# Mem_Switch_V1_1.net
KiCad netlist of a schematic drawn in EAGLE
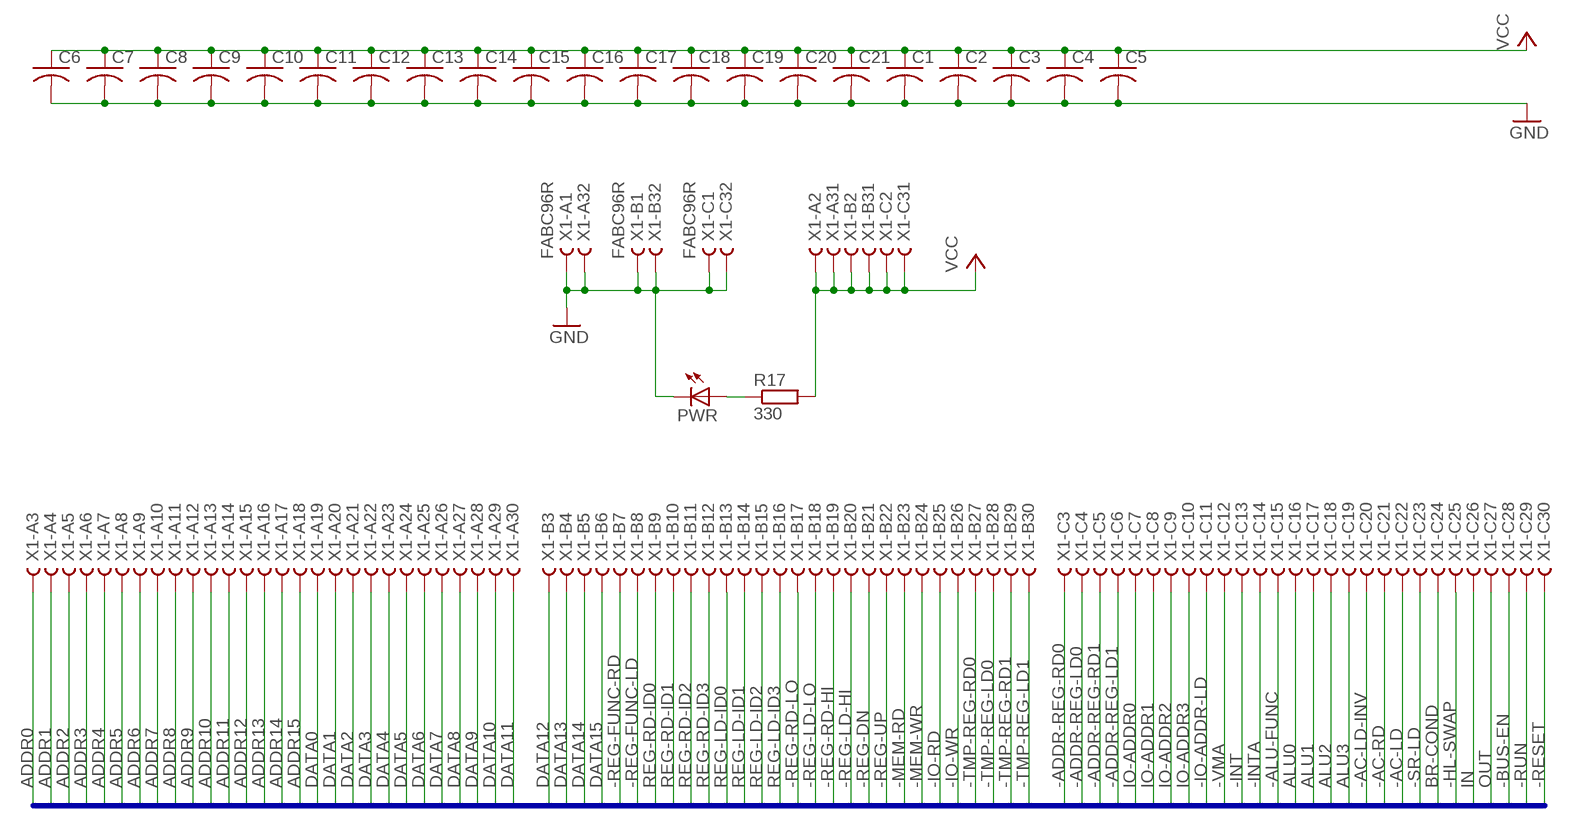
[diagram p0: schematic, sheet 1]
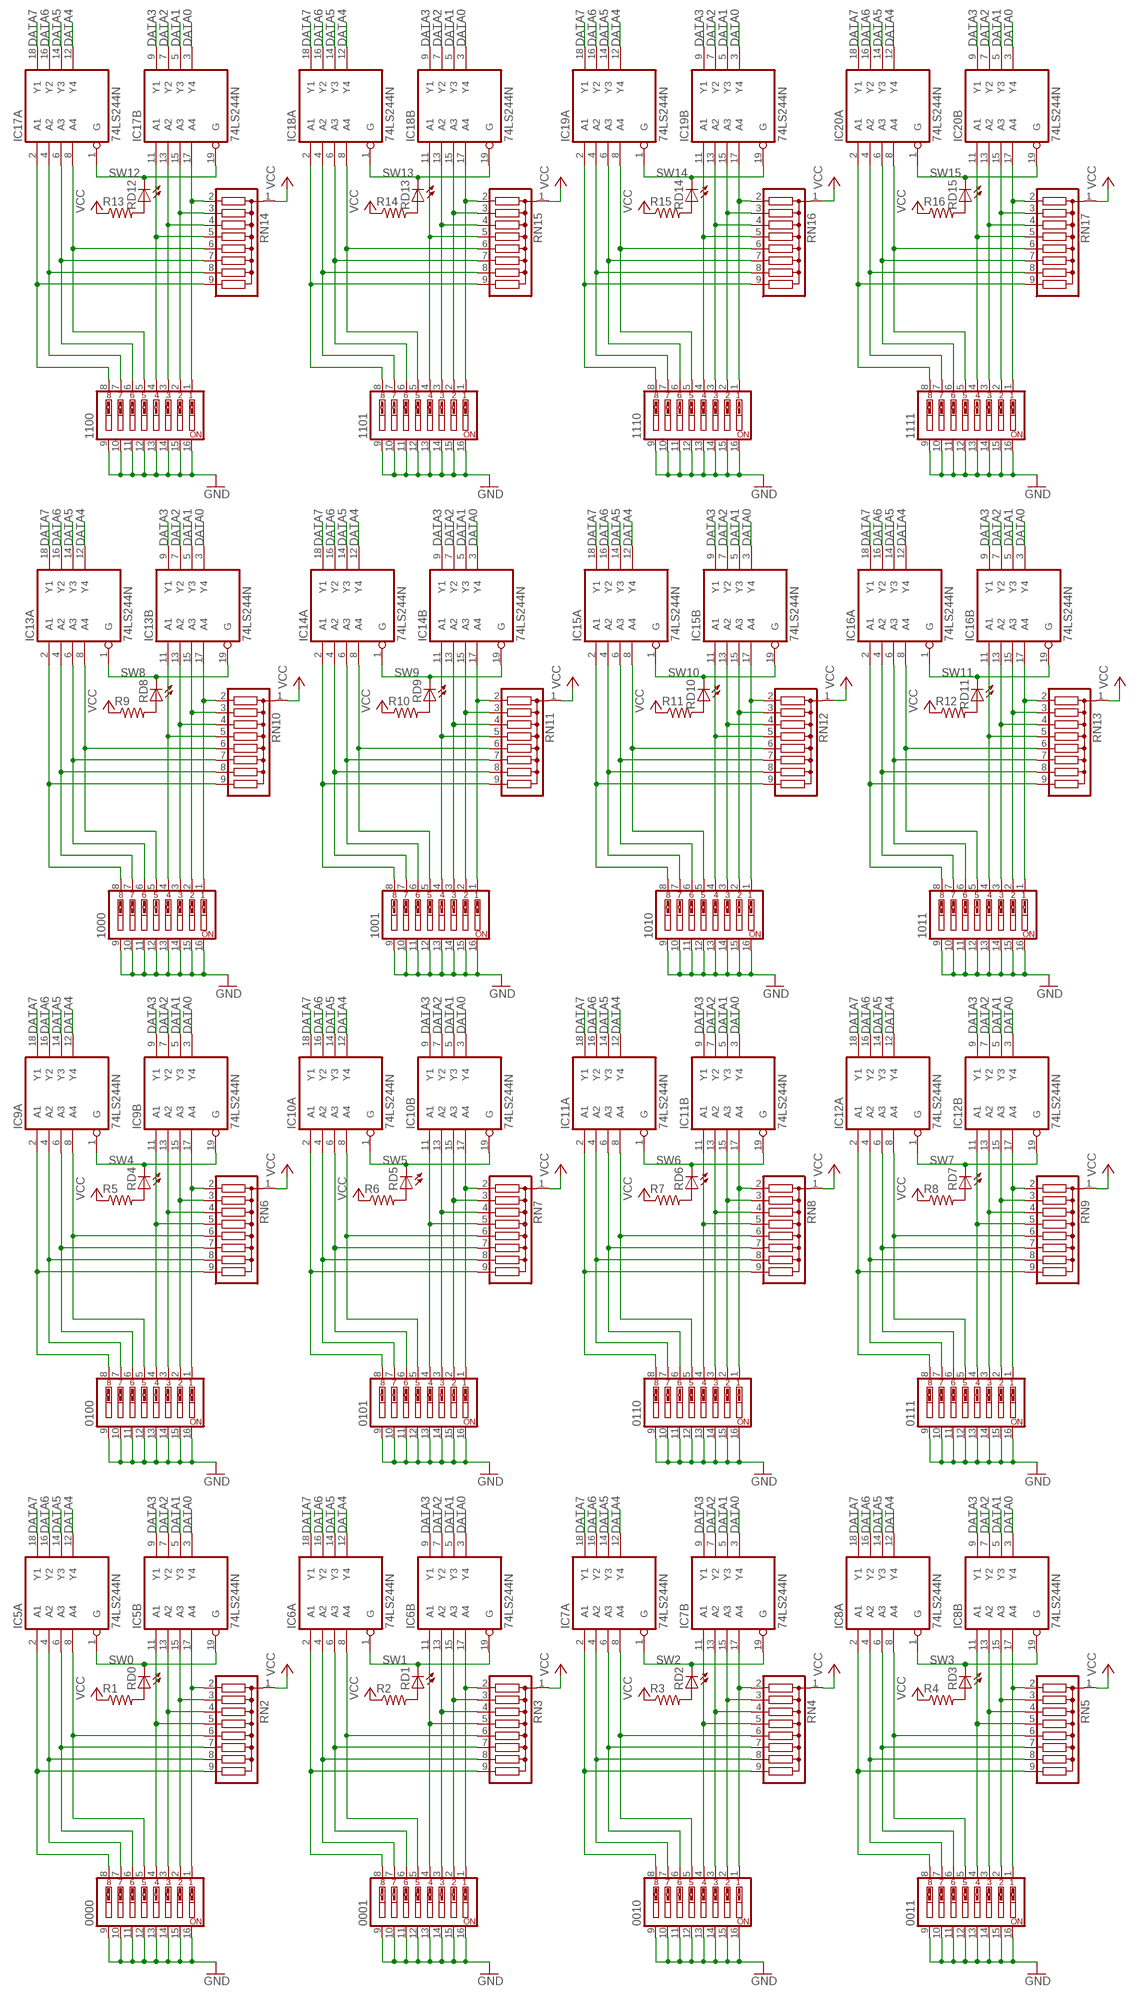
[diagram p1: schematic, sheet 2]
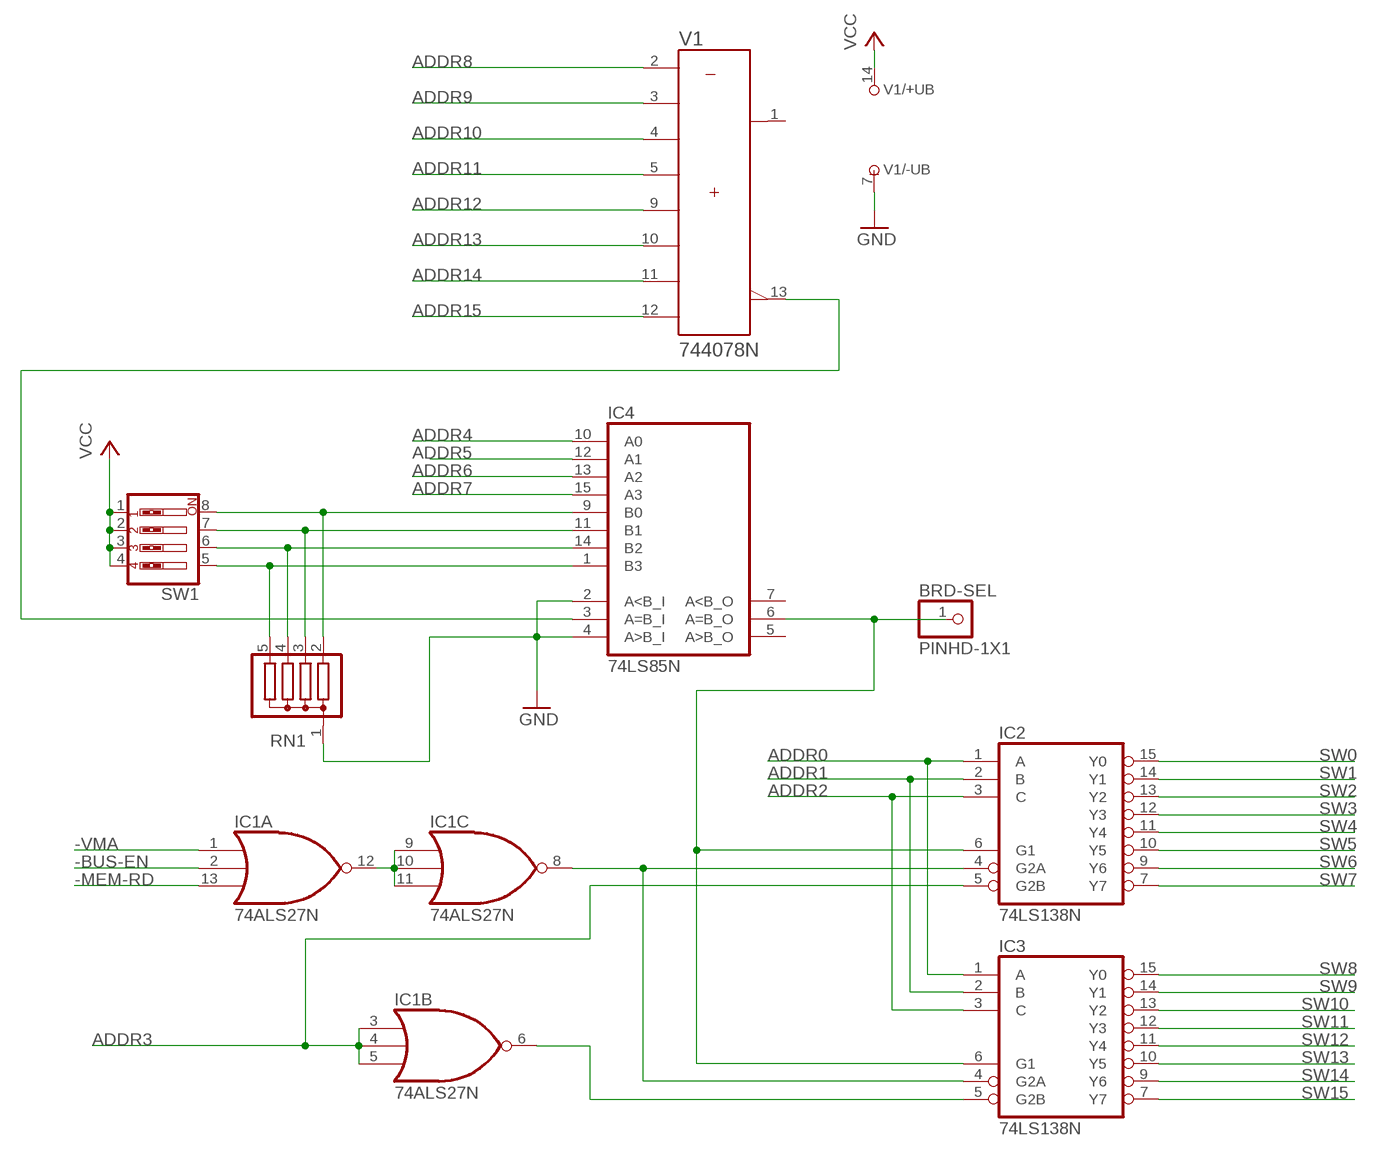
[diagram p2: schematic, sheet 3]

(export (version "E")
  (design (tool "Eeschema 10.0.6"))
  (components
    (comp (ref "0000")
      (value "SW_DIP-8")
      (footprint "eagle-import:EDG-08")
      (libsource (lib "eagle-import") (part "SW_DIP-8"))
    )
    (comp (ref "0001")
      (value "SW_DIP-8")
      (footprint "eagle-import:EDG-08")
      (libsource (lib "eagle-import") (part "SW_DIP-8"))
    )
    (comp (ref "0010")
      (value "SW_DIP-8")
      (footprint "eagle-import:EDG-08")
      (libsource (lib "eagle-import") (part "SW_DIP-8"))
    )
    (comp (ref "0011")
      (value "SW_DIP-8")
      (footprint "eagle-import:EDG-08")
      (libsource (lib "eagle-import") (part "SW_DIP-8"))
    )
    (comp (ref "0100")
      (value "SW_DIP-8")
      (footprint "eagle-import:EDG-08")
      (libsource (lib "eagle-import") (part "SW_DIP-8"))
    )
    (comp (ref "0101")
      (value "SW_DIP-8")
      (footprint "eagle-import:EDG-08")
      (libsource (lib "eagle-import") (part "SW_DIP-8"))
    )
    (comp (ref "0110")
      (value "SW_DIP-8")
      (footprint "eagle-import:EDG-08")
      (libsource (lib "eagle-import") (part "SW_DIP-8"))
    )
    (comp (ref "0111")
      (value "SW_DIP-8")
      (footprint "eagle-import:EDG-08")
      (libsource (lib "eagle-import") (part "SW_DIP-8"))
    )
    (comp (ref "1000")
      (value "SW_DIP-8")
      (footprint "eagle-import:EDG-08")
      (libsource (lib "eagle-import") (part "SW_DIP-8"))
    )
    (comp (ref "1001")
      (value "SW_DIP-8")
      (footprint "eagle-import:EDG-08")
      (libsource (lib "eagle-import") (part "SW_DIP-8"))
    )
    (comp (ref "1010")
      (value "SW_DIP-8")
      (footprint "eagle-import:EDG-08")
      (libsource (lib "eagle-import") (part "SW_DIP-8"))
    )
    (comp (ref "1011")
      (value "SW_DIP-8")
      (footprint "eagle-import:EDG-08")
      (libsource (lib "eagle-import") (part "SW_DIP-8"))
    )
    (comp (ref "1100")
      (value "SW_DIP-8")
      (footprint "eagle-import:EDG-08")
      (libsource (lib "eagle-import") (part "SW_DIP-8"))
    )
    (comp (ref "1101")
      (value "SW_DIP-8")
      (footprint "eagle-import:EDG-08")
      (libsource (lib "eagle-import") (part "SW_DIP-8"))
    )
    (comp (ref "1110")
      (value "SW_DIP-8")
      (footprint "eagle-import:EDG-08")
      (libsource (lib "eagle-import") (part "SW_DIP-8"))
    )
    (comp (ref "1111")
      (value "SW_DIP-8")
      (footprint "eagle-import:EDG-08")
      (libsource (lib "eagle-import") (part "SW_DIP-8"))
    )
    (comp (ref "IC5")
      (value "74LS244N")
      (footprint "eagle-import:DIL20")
      (libsource (lib "eagle-import") (part "74xx-us_88_74244NLS"))
    )
    (comp (ref "IC6")
      (value "74LS244N")
      (footprint "eagle-import:DIL20")
      (libsource (lib "eagle-import") (part "74xx-us_88_74244NLS"))
    )
    (comp (ref "IC7")
      (value "74LS244N")
      (footprint "eagle-import:DIL20")
      (libsource (lib "eagle-import") (part "74xx-us_88_74244NLS"))
    )
    (comp (ref "IC8")
      (value "74LS244N")
      (footprint "eagle-import:DIL20")
      (libsource (lib "eagle-import") (part "74xx-us_88_74244NLS"))
    )
    (comp (ref "IC9")
      (value "74LS244N")
      (footprint "eagle-import:DIL20")
      (libsource (lib "eagle-import") (part "74xx-us_88_74244NLS"))
    )
    (comp (ref "IC10")
      (value "74LS244N")
      (footprint "eagle-import:DIL20")
      (libsource (lib "eagle-import") (part "74xx-us_88_74244NLS"))
    )
    (comp (ref "IC11")
      (value "74LS244N")
      (footprint "eagle-import:DIL20")
      (libsource (lib "eagle-import") (part "74xx-us_88_74244NLS"))
    )
    (comp (ref "IC12")
      (value "74LS244N")
      (footprint "eagle-import:DIL20")
      (libsource (lib "eagle-import") (part "74xx-us_88_74244NLS"))
    )
    (comp (ref "IC13")
      (value "74LS244N")
      (footprint "eagle-import:DIL20")
      (libsource (lib "eagle-import") (part "74xx-us_88_74244NLS"))
    )
    (comp (ref "IC14")
      (value "74LS244N")
      (footprint "eagle-import:DIL20")
      (libsource (lib "eagle-import") (part "74xx-us_88_74244NLS"))
    )
    (comp (ref "IC15")
      (value "74LS244N")
      (footprint "eagle-import:DIL20")
      (libsource (lib "eagle-import") (part "74xx-us_88_74244NLS"))
    )
    (comp (ref "IC16")
      (value "74LS244N")
      (footprint "eagle-import:DIL20")
      (libsource (lib "eagle-import") (part "74xx-us_88_74244NLS"))
    )
    (comp (ref "IC17")
      (value "74LS244N")
      (footprint "eagle-import:DIL20")
      (libsource (lib "eagle-import") (part "74xx-us_88_74244NLS"))
    )
    (comp (ref "IC18")
      (value "74LS244N")
      (footprint "eagle-import:DIL20")
      (libsource (lib "eagle-import") (part "74xx-us_88_74244NLS"))
    )
    (comp (ref "IC19")
      (value "74LS244N")
      (footprint "eagle-import:DIL20")
      (libsource (lib "eagle-import") (part "74xx-us_88_74244NLS"))
    )
    (comp (ref "IC20")
      (value "74LS244N")
      (footprint "eagle-import:DIL20")
      (libsource (lib "eagle-import") (part "74xx-us_88_74244NLS"))
    )
    (comp (ref "R1")
      (value "R-US_0207/10")
      (footprint "eagle-import:0207_10")
      (libsource (lib "eagle-import") (part "R-US_0207/10"))
    )
    (comp (ref "R2")
      (value "R-US_0207/10")
      (footprint "eagle-import:0207_10")
      (libsource (lib "eagle-import") (part "R-US_0207/10"))
    )
    (comp (ref "R3")
      (value "R-US_0207/10")
      (footprint "eagle-import:0207_10")
      (libsource (lib "eagle-import") (part "R-US_0207/10"))
    )
    (comp (ref "R4")
      (value "R-US_0207/10")
      (footprint "eagle-import:0207_10")
      (libsource (lib "eagle-import") (part "R-US_0207/10"))
    )
    (comp (ref "R5")
      (value "R-US_0207/10")
      (footprint "eagle-import:0207_10")
      (libsource (lib "eagle-import") (part "R-US_0207/10"))
    )
    (comp (ref "R6")
      (value "R-US_0207/10")
      (footprint "eagle-import:0207_10")
      (libsource (lib "eagle-import") (part "R-US_0207/10"))
    )
    (comp (ref "R7")
      (value "R-US_0207/10")
      (footprint "eagle-import:0207_10")
      (libsource (lib "eagle-import") (part "R-US_0207/10"))
    )
    (comp (ref "R8")
      (value "R-US_0207/10")
      (footprint "eagle-import:0207_10")
      (libsource (lib "eagle-import") (part "R-US_0207/10"))
    )
    (comp (ref "R9")
      (value "R-US_0207/10")
      (footprint "eagle-import:0207_10")
      (libsource (lib "eagle-import") (part "R-US_0207/10"))
    )
    (comp (ref "R10")
      (value "R-US_0207/10")
      (footprint "eagle-import:0207_10")
      (libsource (lib "eagle-import") (part "R-US_0207/10"))
    )
    (comp (ref "R11")
      (value "R-US_0207/10")
      (footprint "eagle-import:0207_10")
      (libsource (lib "eagle-import") (part "R-US_0207/10"))
    )
    (comp (ref "R12")
      (value "R-US_0207/10")
      (footprint "eagle-import:0207_10")
      (libsource (lib "eagle-import") (part "R-US_0207/10"))
    )
    (comp (ref "R13")
      (value "R-US_0207/10")
      (footprint "eagle-import:0207_10")
      (libsource (lib "eagle-import") (part "R-US_0207/10"))
    )
    (comp (ref "R14")
      (value "R-US_0207/10")
      (footprint "eagle-import:0207_10")
      (libsource (lib "eagle-import") (part "R-US_0207/10"))
    )
    (comp (ref "R15")
      (value "R-US_0207/10")
      (footprint "eagle-import:0207_10")
      (libsource (lib "eagle-import") (part "R-US_0207/10"))
    )
    (comp (ref "R16")
      (value "R-US_0207/10")
      (footprint "eagle-import:0207_10")
      (libsource (lib "eagle-import") (part "R-US_0207/10"))
    )
    (comp (ref "RD0")
      (value "LED3MM")
      (footprint "eagle-import:LED3MM")
      (libsource (lib "eagle-import") (part "LED3MM"))
    )
    (comp (ref "RD1")
      (value "LED3MM")
      (footprint "eagle-import:LED3MM")
      (libsource (lib "eagle-import") (part "LED3MM"))
    )
    (comp (ref "RD2")
      (value "LED3MM")
      (footprint "eagle-import:LED3MM")
      (libsource (lib "eagle-import") (part "LED3MM"))
    )
    (comp (ref "RD3")
      (value "LED3MM")
      (footprint "eagle-import:LED3MM")
      (libsource (lib "eagle-import") (part "LED3MM"))
    )
    (comp (ref "RD4")
      (value "LED3MM")
      (footprint "eagle-import:LED3MM")
      (libsource (lib "eagle-import") (part "LED3MM"))
    )
    (comp (ref "RD5")
      (value "LED3MM")
      (footprint "eagle-import:LED3MM")
      (libsource (lib "eagle-import") (part "LED3MM"))
    )
    (comp (ref "RD6")
      (value "LED3MM")
      (footprint "eagle-import:LED3MM")
      (libsource (lib "eagle-import") (part "LED3MM"))
    )
    (comp (ref "RD7")
      (value "LED3MM")
      (footprint "eagle-import:LED3MM")
      (libsource (lib "eagle-import") (part "LED3MM"))
    )
    (comp (ref "RD8")
      (value "LED3MM")
      (footprint "eagle-import:LED3MM")
      (libsource (lib "eagle-import") (part "LED3MM"))
    )
    (comp (ref "RD9")
      (value "LED3MM")
      (footprint "eagle-import:LED3MM")
      (libsource (lib "eagle-import") (part "LED3MM"))
    )
    (comp (ref "RD10")
      (value "LED3MM")
      (footprint "eagle-import:LED3MM")
      (libsource (lib "eagle-import") (part "LED3MM"))
    )
    (comp (ref "RD11")
      (value "LED3MM")
      (footprint "eagle-import:LED3MM")
      (libsource (lib "eagle-import") (part "LED3MM"))
    )
    (comp (ref "RD12")
      (value "LED3MM")
      (footprint "eagle-import:LED3MM")
      (libsource (lib "eagle-import") (part "LED3MM"))
    )
    (comp (ref "RD13")
      (value "LED3MM")
      (footprint "eagle-import:LED3MM")
      (libsource (lib "eagle-import") (part "LED3MM"))
    )
    (comp (ref "RD14")
      (value "LED3MM")
      (footprint "eagle-import:LED3MM")
      (libsource (lib "eagle-import") (part "LED3MM"))
    )
    (comp (ref "RD15")
      (value "LED3MM")
      (footprint "eagle-import:LED3MM")
      (libsource (lib "eagle-import") (part "LED3MM"))
    )
    (comp (ref "RN2")
      (value "G08R")
      (footprint "eagle-import:SIL9")
      (libsource (lib "eagle-import") (part "G08R"))
    )
    (comp (ref "RN3")
      (value "G08R")
      (footprint "eagle-import:SIL9")
      (libsource (lib "eagle-import") (part "G08R"))
    )
    (comp (ref "RN4")
      (value "G08R")
      (footprint "eagle-import:SIL9")
      (libsource (lib "eagle-import") (part "G08R"))
    )
    (comp (ref "RN5")
      (value "G08R")
      (footprint "eagle-import:SIL9")
      (libsource (lib "eagle-import") (part "G08R"))
    )
    (comp (ref "RN6")
      (value "G08R")
      (footprint "eagle-import:SIL9")
      (libsource (lib "eagle-import") (part "G08R"))
    )
    (comp (ref "RN7")
      (value "G08R")
      (footprint "eagle-import:SIL9")
      (libsource (lib "eagle-import") (part "G08R"))
    )
    (comp (ref "RN8")
      (value "G08R")
      (footprint "eagle-import:SIL9")
      (libsource (lib "eagle-import") (part "G08R"))
    )
    (comp (ref "RN9")
      (value "G08R")
      (footprint "eagle-import:SIL9")
      (libsource (lib "eagle-import") (part "G08R"))
    )
    (comp (ref "RN10")
      (value "G08R")
      (footprint "eagle-import:SIL9")
      (libsource (lib "eagle-import") (part "G08R"))
    )
    (comp (ref "RN11")
      (value "G08R")
      (footprint "eagle-import:SIL9")
      (libsource (lib "eagle-import") (part "G08R"))
    )
    (comp (ref "RN12")
      (value "G08R")
      (footprint "eagle-import:SIL9")
      (libsource (lib "eagle-import") (part "G08R"))
    )
    (comp (ref "RN13")
      (value "G08R")
      (footprint "eagle-import:SIL9")
      (libsource (lib "eagle-import") (part "G08R"))
    )
    (comp (ref "RN14")
      (value "G08R")
      (footprint "eagle-import:SIL9")
      (libsource (lib "eagle-import") (part "G08R"))
    )
    (comp (ref "RN15")
      (value "G08R")
      (footprint "eagle-import:SIL9")
      (libsource (lib "eagle-import") (part "G08R"))
    )
    (comp (ref "RN16")
      (value "G08R")
      (footprint "eagle-import:SIL9")
      (libsource (lib "eagle-import") (part "G08R"))
    )
    (comp (ref "RN17")
      (value "G08R")
      (footprint "eagle-import:SIL9")
      (libsource (lib "eagle-import") (part "G08R"))
    )
    (comp (ref "C1")
      (value "C-US025-025X050")
      (footprint "eagle-import:C025-025X050")
      (libsource (lib "eagle-import") (part "C-US025-025X050"))
    )
    (comp (ref "C2")
      (value "C-US025-025X050")
      (footprint "eagle-import:C025-025X050")
      (libsource (lib "eagle-import") (part "C-US025-025X050"))
    )
    (comp (ref "C3")
      (value "C-US025-025X050")
      (footprint "eagle-import:C025-025X050")
      (libsource (lib "eagle-import") (part "C-US025-025X050"))
    )
    (comp (ref "C4")
      (value "C-US025-025X050")
      (footprint "eagle-import:C025-025X050")
      (libsource (lib "eagle-import") (part "C-US025-025X050"))
    )
    (comp (ref "C5")
      (value "C-US025-025X050")
      (footprint "eagle-import:C025-025X050")
      (libsource (lib "eagle-import") (part "C-US025-025X050"))
    )
    (comp (ref "C6")
      (value "C-US025-025X050")
      (footprint "eagle-import:C025-025X050")
      (libsource (lib "eagle-import") (part "C-US025-025X050"))
    )
    (comp (ref "C7")
      (value "C-US025-025X050")
      (footprint "eagle-import:C025-025X050")
      (libsource (lib "eagle-import") (part "C-US025-025X050"))
    )
    (comp (ref "C8")
      (value "C-US025-025X050")
      (footprint "eagle-import:C025-025X050")
      (libsource (lib "eagle-import") (part "C-US025-025X050"))
    )
    (comp (ref "C9")
      (value "C-US025-025X050")
      (footprint "eagle-import:C025-025X050")
      (libsource (lib "eagle-import") (part "C-US025-025X050"))
    )
    (comp (ref "C10")
      (value "C-US025-025X050")
      (footprint "eagle-import:C025-025X050")
      (libsource (lib "eagle-import") (part "C-US025-025X050"))
    )
    (comp (ref "C11")
      (value "C-US025-025X050")
      (footprint "eagle-import:C025-025X050")
      (libsource (lib "eagle-import") (part "C-US025-025X050"))
    )
    (comp (ref "C12")
      (value "C-US025-025X050")
      (footprint "eagle-import:C025-025X050")
      (libsource (lib "eagle-import") (part "C-US025-025X050"))
    )
    (comp (ref "C13")
      (value "C-US025-025X050")
      (footprint "eagle-import:C025-025X050")
      (libsource (lib "eagle-import") (part "C-US025-025X050"))
    )
    (comp (ref "C14")
      (value "C-US025-025X050")
      (footprint "eagle-import:C025-025X050")
      (libsource (lib "eagle-import") (part "C-US025-025X050"))
    )
    (comp (ref "C15")
      (value "C-US025-025X050")
      (footprint "eagle-import:C025-025X050")
      (libsource (lib "eagle-import") (part "C-US025-025X050"))
    )
    (comp (ref "C16")
      (value "C-US025-025X050")
      (footprint "eagle-import:C025-025X050")
      (libsource (lib "eagle-import") (part "C-US025-025X050"))
    )
    (comp (ref "C17")
      (value "C-US025-025X050")
      (footprint "eagle-import:C025-025X050")
      (libsource (lib "eagle-import") (part "C-US025-025X050"))
    )
    (comp (ref "C18")
      (value "C-US025-025X050")
      (footprint "eagle-import:C025-025X050")
      (libsource (lib "eagle-import") (part "C-US025-025X050"))
    )
    (comp (ref "C19")
      (value "C-US025-025X050")
      (footprint "eagle-import:C025-025X050")
      (libsource (lib "eagle-import") (part "C-US025-025X050"))
    )
    (comp (ref "C20")
      (value "C-US025-025X050")
      (footprint "eagle-import:C025-025X050")
      (libsource (lib "eagle-import") (part "C-US025-025X050"))
    )
    (comp (ref "C21")
      (value "C-US025-025X050")
      (footprint "eagle-import:C025-025X050")
      (libsource (lib "eagle-import") (part "C-US025-025X050"))
    )
    (comp (ref "PWR")
      (value "LED5MM")
      (footprint "eagle-import:LED5MM")
      (libsource (lib "eagle-import") (part "led_LED5MM"))
    )
    (comp (ref "R17")
      (value "330")
      (footprint "eagle-import:0207_10")
      (libsource (lib "eagle-import") (part "R0207/10"))
    )
    (comp (ref "X1")
      (value "FABC96R")
      (footprint "eagle-import:FABC96R")
      (libsource (lib "eagle-import") (part "FABC96R"))
    )
    (comp (ref "BRD-SEL")
      (value "PINHD-1X1")
      (footprint "eagle-import:1X01")
      (libsource (lib "eagle-import") (part "PINHD-1X1"))
    )
    (comp (ref "IC1")
      (value "74ALS27N")
      (footprint "eagle-import:DIL14")
      (libsource (lib "eagle-import") (part "7427NALS"))
    )
    (comp (ref "IC2")
      (value "74LS138N")
      (footprint "eagle-import:DIL16")
      (libsource (lib "eagle-import") (part "74138NLS"))
    )
    (comp (ref "IC3")
      (value "74LS138N")
      (footprint "eagle-import:DIL16")
      (libsource (lib "eagle-import") (part "74138NLS"))
    )
    (comp (ref "IC4")
      (value "74LS85N")
      (footprint "eagle-import:DIL16")
      (libsource (lib "eagle-import") (part "7485NLS"))
    )
    (comp (ref "RN1")
      (value "G04R")
      (footprint "eagle-import:SIL5")
      (libsource (lib "eagle-import") (part "G04R"))
    )
    (comp (ref "SW1")
      (value "SW_DIP-4")
      (footprint "eagle-import:EDG-04")
      (libsource (lib "eagle-import") (part "SW_DIP-4"))
    )
    (comp (ref "V1")
      (value "744078N")
      (footprint "eagle-import:DIL14")
      (libsource (lib "eagle-import") (part "744078N"))
    )
  )
  (nets
    (net (code "1") (name "-AC-LD") (class "Default")
      (node (ref "X1") (pin "C22") (pinfunction "B_C22") (pintype "passive"))
    )
    (net (code "2") (name "-AC-LD-INV") (class "Default")
      (node (ref "X1") (pin "C20") (pinfunction "B_C20") (pintype "passive"))
    )
    (net (code "3") (name "-AC-RD") (class "Default")
      (node (ref "X1") (pin "C21") (pinfunction "B_C21") (pintype "passive"))
    )
    (net (code "4") (name "-ADDR-REG-LD0") (class "Default")
      (node (ref "X1") (pin "C4") (pinfunction "B_C4") (pintype "passive"))
    )
    (net (code "5") (name "-ADDR-REG-LD1") (class "Default")
      (node (ref "X1") (pin "C6") (pinfunction "B_C6") (pintype "passive"))
    )
    (net (code "6") (name "-ADDR-REG-RD0") (class "Default")
      (node (ref "X1") (pin "C3") (pinfunction "B_C3") (pintype "passive"))
    )
    (net (code "7") (name "-ADDR-REG-RD1") (class "Default")
      (node (ref "X1") (pin "C5") (pinfunction "B_C5") (pintype "passive"))
    )
    (net (code "8") (name "-ALU-FUNC") (class "Default")
      (node (ref "X1") (pin "C15") (pinfunction "B_C15") (pintype "passive"))
    )
    (net (code "9") (name "-BUS-EN") (class "Default")
      (node (ref "IC1") (pin "2") (pinfunction "I1_2") (pintype "input"))
      (node (ref "X1") (pin "C28") (pinfunction "B_C28") (pintype "passive"))
    )
    (net (code "10") (name "-HL-SWAP") (class "Default")
      (node (ref "X1") (pin "C25") (pinfunction "B_C25") (pintype "passive"))
    )
    (net (code "11") (name "-INT") (class "Default")
      (node (ref "X1") (pin "C13") (pinfunction "B_C13") (pintype "passive"))
    )
    (net (code "12") (name "-INTA") (class "Default")
      (node (ref "X1") (pin "C14") (pinfunction "B_C14") (pintype "passive"))
    )
    (net (code "13") (name "-IO-ADDR-LD") (class "Default")
      (node (ref "X1") (pin "C11") (pinfunction "B_C11") (pintype "passive"))
    )
    (net (code "14") (name "-IO-RD") (class "Default")
      (node (ref "X1") (pin "B25") (pinfunction "B_B25") (pintype "passive"))
    )
    (net (code "15") (name "-IO-WR") (class "Default")
      (node (ref "X1") (pin "B26") (pinfunction "B_B26") (pintype "passive"))
    )
    (net (code "16") (name "-MEM-RD") (class "Default")
      (node (ref "IC1") (pin "13") (pinfunction "I2_13") (pintype "input"))
      (node (ref "X1") (pin "B23") (pinfunction "B_B23") (pintype "passive"))
    )
    (net (code "17") (name "-MEM-WR") (class "Default")
      (node (ref "X1") (pin "B24") (pinfunction "B_B24") (pintype "passive"))
    )
    (net (code "18") (name "-REG-DN") (class "Default")
      (node (ref "X1") (pin "B21") (pinfunction "B_B21") (pintype "passive"))
    )
    (net (code "19") (name "-REG-FUNC-LD") (class "Default")
      (node (ref "X1") (pin "B8") (pinfunction "B_B8") (pintype "passive"))
    )
    (net (code "20") (name "-REG-FUNC-RD") (class "Default")
      (node (ref "X1") (pin "B7") (pinfunction "B_B7") (pintype "passive"))
    )
    (net (code "21") (name "-REG-LD-HI") (class "Default")
      (node (ref "X1") (pin "B20") (pinfunction "B_B20") (pintype "passive"))
    )
    (net (code "22") (name "-REG-LD-LO") (class "Default")
      (node (ref "X1") (pin "B18") (pinfunction "B_B18") (pintype "passive"))
    )
    (net (code "23") (name "-REG-RD-HI") (class "Default")
      (node (ref "X1") (pin "B19") (pinfunction "B_B19") (pintype "passive"))
    )
    (net (code "24") (name "-REG-RD-LO") (class "Default")
      (node (ref "X1") (pin "B17") (pinfunction "B_B17") (pintype "passive"))
    )
    (net (code "25") (name "-REG-UP") (class "Default")
      (node (ref "X1") (pin "B22") (pinfunction "B_B22") (pintype "passive"))
    )
    (net (code "26") (name "-RESET") (class "Default")
      (node (ref "X1") (pin "C30") (pinfunction "B_C30") (pintype "passive"))
    )
    (net (code "27") (name "-RUN") (class "Default")
      (node (ref "X1") (pin "C29") (pinfunction "B_C29") (pintype "passive"))
    )
    (net (code "28") (name "-SR-LD") (class "Default")
      (node (ref "X1") (pin "C23") (pinfunction "B_C23") (pintype "passive"))
    )
    (net (code "29") (name "-TMP-REG-LD0") (class "Default")
      (node (ref "X1") (pin "B28") (pinfunction "B_B28") (pintype "passive"))
    )
    (net (code "30") (name "-TMP-REG-LD1") (class "Default")
      (node (ref "X1") (pin "B30") (pinfunction "B_B30") (pintype "passive"))
    )
    (net (code "31") (name "-TMP-REG-RD0") (class "Default")
      (node (ref "X1") (pin "B27") (pinfunction "B_B27") (pintype "passive"))
    )
    (net (code "32") (name "-TMP-REG-RD1") (class "Default")
      (node (ref "X1") (pin "B29") (pinfunction "B_B29") (pintype "passive"))
    )
    (net (code "33") (name "-VMA") (class "Default")
      (node (ref "IC1") (pin "1") (pinfunction "I0_1") (pintype "input"))
      (node (ref "X1") (pin "C12") (pinfunction "B_C12") (pintype "passive"))
    )
    (net (code "34") (name "ADDR0") (class "Default")
      (node (ref "IC2") (pin "1") (pinfunction "A_1") (pintype "input"))
      (node (ref "IC3") (pin "1") (pinfunction "A_1") (pintype "input"))
      (node (ref "X1") (pin "A3") (pinfunction "B_A3") (pintype "passive"))
    )
    (net (code "35") (name "ADDR1") (class "Default")
      (node (ref "IC2") (pin "2") (pinfunction "B_2") (pintype "input"))
      (node (ref "IC3") (pin "2") (pinfunction "B_2") (pintype "input"))
      (node (ref "X1") (pin "A4") (pinfunction "B_A4") (pintype "passive"))
    )
    (net (code "36") (name "ADDR2") (class "Default")
      (node (ref "IC2") (pin "3") (pinfunction "C_3") (pintype "input"))
      (node (ref "IC3") (pin "3") (pinfunction "C_3") (pintype "input"))
      (node (ref "X1") (pin "A5") (pinfunction "B_A5") (pintype "passive"))
    )
    (net (code "37") (name "ADDR3") (class "Default")
      (node (ref "IC1") (pin "3") (pinfunction "I0_3") (pintype "input"))
      (node (ref "IC1") (pin "4") (pinfunction "I1_4") (pintype "input"))
      (node (ref "IC1") (pin "5") (pinfunction "I2_5") (pintype "input"))
      (node (ref "IC2") (pin "5") (pinfunction "G2B_5") (pintype "input"))
      (node (ref "X1") (pin "A6") (pinfunction "B_A6") (pintype "passive"))
    )
    (net (code "38") (name "ADDR4") (class "Default")
      (node (ref "IC4") (pin "10") (pinfunction "A0_10") (pintype "input"))
      (node (ref "X1") (pin "A7") (pinfunction "B_A7") (pintype "passive"))
    )
    (net (code "39") (name "ADDR5") (class "Default")
      (node (ref "IC4") (pin "12") (pinfunction "A1_12") (pintype "input"))
      (node (ref "X1") (pin "A8") (pinfunction "B_A8") (pintype "passive"))
    )
    (net (code "40") (name "ADDR6") (class "Default")
      (node (ref "IC4") (pin "13") (pinfunction "A2_13") (pintype "input"))
      (node (ref "X1") (pin "A9") (pinfunction "B_A9") (pintype "passive"))
    )
    (net (code "41") (name "ADDR7") (class "Default")
      (node (ref "IC4") (pin "15") (pinfunction "A3_15") (pintype "input"))
      (node (ref "X1") (pin "A10") (pinfunction "B_A10") (pintype "passive"))
    )
    (net (code "42") (name "ADDR8") (class "Default")
      (node (ref "V1") (pin "2") (pinfunction "A_2") (pintype "input"))
      (node (ref "X1") (pin "A11") (pinfunction "B_A11") (pintype "passive"))
    )
    (net (code "43") (name "ADDR9") (class "Default")
      (node (ref "V1") (pin "3") (pinfunction "B_3") (pintype "input"))
      (node (ref "X1") (pin "A12") (pinfunction "B_A12") (pintype "passive"))
    )
    (net (code "44") (name "ADDR10") (class "Default")
      (node (ref "V1") (pin "4") (pinfunction "C_4") (pintype "input"))
      (node (ref "X1") (pin "A13") (pinfunction "B_A13") (pintype "passive"))
    )
    (net (code "45") (name "ADDR11") (class "Default")
      (node (ref "V1") (pin "5") (pinfunction "D_5") (pintype "input"))
      (node (ref "X1") (pin "A14") (pinfunction "B_A14") (pintype "passive"))
    )
    (net (code "46") (name "ADDR12") (class "Default")
      (node (ref "V1") (pin "9") (pinfunction "E_9") (pintype "input"))
      (node (ref "X1") (pin "A15") (pinfunction "B_A15") (pintype "passive"))
    )
    (net (code "47") (name "ADDR13") (class "Default")
      (node (ref "V1") (pin "10") (pinfunction "F_10") (pintype "input"))
      (node (ref "X1") (pin "A16") (pinfunction "B_A16") (pintype "passive"))
    )
    (net (code "48") (name "ADDR14") (class "Default")
      (node (ref "V1") (pin "11") (pinfunction "G_11") (pintype "input"))
      (node (ref "X1") (pin "A17") (pinfunction "B_A17") (pintype "passive"))
    )
    (net (code "49") (name "ADDR15") (class "Default")
      (node (ref "V1") (pin "12") (pinfunction "H_12") (pintype "input"))
      (node (ref "X1") (pin "A18") (pinfunction "B_A18") (pintype "passive"))
    )
    (net (code "50") (name "ALU0") (class "Default")
      (node (ref "X1") (pin "C16") (pinfunction "B_C16") (pintype "passive"))
    )
    (net (code "51") (name "ALU1") (class "Default")
      (node (ref "X1") (pin "C17") (pinfunction "B_C17") (pintype "passive"))
    )
    (net (code "52") (name "ALU2") (class "Default")
      (node (ref "X1") (pin "C18") (pinfunction "B_C18") (pintype "passive"))
    )
    (net (code "53") (name "ALU3") (class "Default")
      (node (ref "X1") (pin "C19") (pinfunction "B_C19") (pintype "passive"))
    )
    (net (code "54") (name "BR-COND") (class "Default")
      (node (ref "X1") (pin "C24") (pinfunction "B_C24") (pintype "passive"))
    )
    (net (code "55") (name "DATA0") (class "Default")
      (node (ref "IC10") (pin "3") (pinfunction "Y4_3") (pintype "tri_state"))
      (node (ref "IC11") (pin "3") (pinfunction "Y4_3") (pintype "tri_state"))
      (node (ref "IC12") (pin "3") (pinfunction "Y4_3") (pintype "tri_state"))
      (node (ref "IC13") (pin "3") (pinfunction "Y4_3") (pintype "tri_state"))
      (node (ref "IC14") (pin "3") (pinfunction "Y4_3") (pintype "tri_state"))
      (node (ref "IC15") (pin "3") (pinfunction "Y4_3") (pintype "tri_state"))
      (node (ref "IC16") (pin "3") (pinfunction "Y4_3") (pintype "tri_state"))
      (node (ref "IC17") (pin "3") (pinfunction "Y4_3") (pintype "tri_state"))
      (node (ref "IC18") (pin "3") (pinfunction "Y4_3") (pintype "tri_state"))
      (node (ref "IC19") (pin "3") (pinfunction "Y4_3") (pintype "tri_state"))
      (node (ref "IC20") (pin "3") (pinfunction "Y4_3") (pintype "tri_state"))
      (node (ref "IC5") (pin "3") (pinfunction "Y4_3") (pintype "tri_state"))
      (node (ref "IC6") (pin "3") (pinfunction "Y4_3") (pintype "tri_state"))
      (node (ref "IC7") (pin "3") (pinfunction "Y4_3") (pintype "tri_state"))
      (node (ref "IC8") (pin "3") (pinfunction "Y4_3") (pintype "tri_state"))
      (node (ref "IC9") (pin "3") (pinfunction "Y4_3") (pintype "tri_state"))
      (node (ref "X1") (pin "A19") (pinfunction "B_A19") (pintype "passive"))
    )
    (net (code "56") (name "DATA1") (class "Default")
      (node (ref "IC10") (pin "5") (pinfunction "Y3_5") (pintype "tri_state"))
      (node (ref "IC11") (pin "5") (pinfunction "Y3_5") (pintype "tri_state"))
      (node (ref "IC12") (pin "5") (pinfunction "Y3_5") (pintype "tri_state"))
      (node (ref "IC13") (pin "5") (pinfunction "Y3_5") (pintype "tri_state"))
      (node (ref "IC14") (pin "5") (pinfunction "Y3_5") (pintype "tri_state"))
      (node (ref "IC15") (pin "5") (pinfunction "Y3_5") (pintype "tri_state"))
      (node (ref "IC16") (pin "5") (pinfunction "Y3_5") (pintype "tri_state"))
      (node (ref "IC17") (pin "5") (pinfunction "Y3_5") (pintype "tri_state"))
      (node (ref "IC18") (pin "5") (pinfunction "Y3_5") (pintype "tri_state"))
      (node (ref "IC19") (pin "5") (pinfunction "Y3_5") (pintype "tri_state"))
      (node (ref "IC20") (pin "5") (pinfunction "Y3_5") (pintype "tri_state"))
      (node (ref "IC5") (pin "5") (pinfunction "Y3_5") (pintype "tri_state"))
      (node (ref "IC6") (pin "5") (pinfunction "Y3_5") (pintype "tri_state"))
      (node (ref "IC7") (pin "5") (pinfunction "Y3_5") (pintype "tri_state"))
      (node (ref "IC8") (pin "5") (pinfunction "Y3_5") (pintype "tri_state"))
      (node (ref "IC9") (pin "5") (pinfunction "Y3_5") (pintype "tri_state"))
      (node (ref "X1") (pin "A20") (pinfunction "B_A20") (pintype "passive"))
    )
    (net (code "57") (name "DATA2") (class "Default")
      (node (ref "IC10") (pin "7") (pinfunction "Y2_7") (pintype "tri_state"))
      (node (ref "IC11") (pin "7") (pinfunction "Y2_7") (pintype "tri_state"))
      (node (ref "IC12") (pin "7") (pinfunction "Y2_7") (pintype "tri_state"))
      (node (ref "IC13") (pin "7") (pinfunction "Y2_7") (pintype "tri_state"))
      (node (ref "IC14") (pin "7") (pinfunction "Y2_7") (pintype "tri_state"))
      (node (ref "IC15") (pin "7") (pinfunction "Y2_7") (pintype "tri_state"))
      (node (ref "IC16") (pin "7") (pinfunction "Y2_7") (pintype "tri_state"))
      (node (ref "IC17") (pin "7") (pinfunction "Y2_7") (pintype "tri_state"))
      (node (ref "IC18") (pin "7") (pinfunction "Y2_7") (pintype "tri_state"))
      (node (ref "IC19") (pin "7") (pinfunction "Y2_7") (pintype "tri_state"))
      (node (ref "IC20") (pin "7") (pinfunction "Y2_7") (pintype "tri_state"))
      (node (ref "IC5") (pin "7") (pinfunction "Y2_7") (pintype "tri_state"))
      (node (ref "IC6") (pin "7") (pinfunction "Y2_7") (pintype "tri_state"))
      (node (ref "IC7") (pin "7") (pinfunction "Y2_7") (pintype "tri_state"))
      (node (ref "IC8") (pin "7") (pinfunction "Y2_7") (pintype "tri_state"))
      (node (ref "IC9") (pin "7") (pinfunction "Y2_7") (pintype "tri_state"))
      (node (ref "X1") (pin "A21") (pinfunction "B_A21") (pintype "passive"))
    )
    (net (code "58") (name "DATA3") (class "Default")
      (node (ref "IC10") (pin "9") (pinfunction "Y1_9") (pintype "tri_state"))
      (node (ref "IC11") (pin "9") (pinfunction "Y1_9") (pintype "tri_state"))
      (node (ref "IC12") (pin "9") (pinfunction "Y1_9") (pintype "tri_state"))
      (node (ref "IC13") (pin "9") (pinfunction "Y1_9") (pintype "tri_state"))
      (node (ref "IC14") (pin "9") (pinfunction "Y1_9") (pintype "tri_state"))
      (node (ref "IC15") (pin "9") (pinfunction "Y1_9") (pintype "tri_state"))
      (node (ref "IC16") (pin "9") (pinfunction "Y1_9") (pintype "tri_state"))
      (node (ref "IC17") (pin "9") (pinfunction "Y1_9") (pintype "tri_state"))
      (node (ref "IC18") (pin "9") (pinfunction "Y1_9") (pintype "tri_state"))
      (node (ref "IC19") (pin "9") (pinfunction "Y1_9") (pintype "tri_state"))
      (node (ref "IC20") (pin "9") (pinfunction "Y1_9") (pintype "tri_state"))
      (node (ref "IC5") (pin "9") (pinfunction "Y1_9") (pintype "tri_state"))
      (node (ref "IC6") (pin "9") (pinfunction "Y1_9") (pintype "tri_state"))
      (node (ref "IC7") (pin "9") (pinfunction "Y1_9") (pintype "tri_state"))
      (node (ref "IC8") (pin "9") (pinfunction "Y1_9") (pintype "tri_state"))
      (node (ref "IC9") (pin "9") (pinfunction "Y1_9") (pintype "tri_state"))
      (node (ref "X1") (pin "A22") (pinfunction "B_A22") (pintype "passive"))
    )
    (net (code "59") (name "DATA4") (class "Default")
      (node (ref "IC10") (pin "12") (pinfunction "Y4_12") (pintype "tri_state"))
      (node (ref "IC11") (pin "12") (pinfunction "Y4_12") (pintype "tri_state"))
      (node (ref "IC12") (pin "12") (pinfunction "Y4_12") (pintype "tri_state"))
      (node (ref "IC13") (pin "12") (pinfunction "Y4_12") (pintype "tri_state"))
      (node (ref "IC14") (pin "12") (pinfunction "Y4_12") (pintype "tri_state"))
      (node (ref "IC15") (pin "12") (pinfunction "Y4_12") (pintype "tri_state"))
      (node (ref "IC16") (pin "12") (pinfunction "Y4_12") (pintype "tri_state"))
      (node (ref "IC17") (pin "12") (pinfunction "Y4_12") (pintype "tri_state"))
      (node (ref "IC18") (pin "12") (pinfunction "Y4_12") (pintype "tri_state"))
      (node (ref "IC19") (pin "12") (pinfunction "Y4_12") (pintype "tri_state"))
      (node (ref "IC20") (pin "12") (pinfunction "Y4_12") (pintype "tri_state"))
      (node (ref "IC5") (pin "12") (pinfunction "Y4_12") (pintype "tri_state"))
      (node (ref "IC6") (pin "12") (pinfunction "Y4_12") (pintype "tri_state"))
      (node (ref "IC7") (pin "12") (pinfunction "Y4_12") (pintype "tri_state"))
      (node (ref "IC8") (pin "12") (pinfunction "Y4_12") (pintype "tri_state"))
      (node (ref "IC9") (pin "12") (pinfunction "Y4_12") (pintype "tri_state"))
      (node (ref "X1") (pin "A23") (pinfunction "B_A23") (pintype "passive"))
    )
    (net (code "60") (name "DATA5") (class "Default")
      (node (ref "IC10") (pin "14") (pinfunction "Y3_14") (pintype "tri_state"))
      (node (ref "IC11") (pin "14") (pinfunction "Y3_14") (pintype "tri_state"))
      (node (ref "IC12") (pin "14") (pinfunction "Y3_14") (pintype "tri_state"))
      (node (ref "IC13") (pin "14") (pinfunction "Y3_14") (pintype "tri_state"))
      (node (ref "IC14") (pin "14") (pinfunction "Y3_14") (pintype "tri_state"))
      (node (ref "IC15") (pin "14") (pinfunction "Y3_14") (pintype "tri_state"))
      (node (ref "IC16") (pin "14") (pinfunction "Y3_14") (pintype "tri_state"))
      (node (ref "IC17") (pin "14") (pinfunction "Y3_14") (pintype "tri_state"))
      (node (ref "IC18") (pin "14") (pinfunction "Y3_14") (pintype "tri_state"))
      (node (ref "IC19") (pin "14") (pinfunction "Y3_14") (pintype "tri_state"))
      (node (ref "IC20") (pin "14") (pinfunction "Y3_14") (pintype "tri_state"))
      (node (ref "IC5") (pin "14") (pinfunction "Y3_14") (pintype "tri_state"))
      (node (ref "IC6") (pin "14") (pinfunction "Y3_14") (pintype "tri_state"))
      (node (ref "IC7") (pin "14") (pinfunction "Y3_14") (pintype "tri_state"))
      (node (ref "IC8") (pin "14") (pinfunction "Y3_14") (pintype "tri_state"))
      (node (ref "IC9") (pin "14") (pinfunction "Y3_14") (pintype "tri_state"))
      (node (ref "X1") (pin "A24") (pinfunction "B_A24") (pintype "passive"))
    )
    (net (code "61") (name "DATA6") (class "Default")
      (node (ref "IC10") (pin "16") (pinfunction "Y2_16") (pintype "tri_state"))
      (node (ref "IC11") (pin "16") (pinfunction "Y2_16") (pintype "tri_state"))
      (node (ref "IC12") (pin "16") (pinfunction "Y2_16") (pintype "tri_state"))
      (node (ref "IC13") (pin "16") (pinfunction "Y2_16") (pintype "tri_state"))
      (node (ref "IC14") (pin "16") (pinfunction "Y2_16") (pintype "tri_state"))
      (node (ref "IC15") (pin "16") (pinfunction "Y2_16") (pintype "tri_state"))
      (node (ref "IC16") (pin "16") (pinfunction "Y2_16") (pintype "tri_state"))
      (node (ref "IC17") (pin "16") (pinfunction "Y2_16") (pintype "tri_state"))
      (node (ref "IC18") (pin "16") (pinfunction "Y2_16") (pintype "tri_state"))
      (node (ref "IC19") (pin "16") (pinfunction "Y2_16") (pintype "tri_state"))
      (node (ref "IC20") (pin "16") (pinfunction "Y2_16") (pintype "tri_state"))
      (node (ref "IC5") (pin "16") (pinfunction "Y2_16") (pintype "tri_state"))
      (node (ref "IC6") (pin "16") (pinfunction "Y2_16") (pintype "tri_state"))
      (node (ref "IC7") (pin "16") (pinfunction "Y2_16") (pintype "tri_state"))
      (node (ref "IC8") (pin "16") (pinfunction "Y2_16") (pintype "tri_state"))
      (node (ref "IC9") (pin "16") (pinfunction "Y2_16") (pintype "tri_state"))
      (node (ref "X1") (pin "A25") (pinfunction "B_A25") (pintype "passive"))
    )
    (net (code "62") (name "DATA7") (class "Default")
      (node (ref "IC10") (pin "18") (pinfunction "Y1_18") (pintype "tri_state"))
      (node (ref "IC11") (pin "18") (pinfunction "Y1_18") (pintype "tri_state"))
      (node (ref "IC12") (pin "18") (pinfunction "Y1_18") (pintype "tri_state"))
      (node (ref "IC13") (pin "18") (pinfunction "Y1_18") (pintype "tri_state"))
      (node (ref "IC14") (pin "18") (pinfunction "Y1_18") (pintype "tri_state"))
      (node (ref "IC15") (pin "18") (pinfunction "Y1_18") (pintype "tri_state"))
      (node (ref "IC16") (pin "18") (pinfunction "Y1_18") (pintype "tri_state"))
      (node (ref "IC17") (pin "18") (pinfunction "Y1_18") (pintype "tri_state"))
      (node (ref "IC18") (pin "18") (pinfunction "Y1_18") (pintype "tri_state"))
      (node (ref "IC19") (pin "18") (pinfunction "Y1_18") (pintype "tri_state"))
      (node (ref "IC20") (pin "18") (pinfunction "Y1_18") (pintype "tri_state"))
      (node (ref "IC5") (pin "18") (pinfunction "Y1_18") (pintype "tri_state"))
      (node (ref "IC6") (pin "18") (pinfunction "Y1_18") (pintype "tri_state"))
      (node (ref "IC7") (pin "18") (pinfunction "Y1_18") (pintype "tri_state"))
      (node (ref "IC8") (pin "18") (pinfunction "Y1_18") (pintype "tri_state"))
      (node (ref "IC9") (pin "18") (pinfunction "Y1_18") (pintype "tri_state"))
      (node (ref "X1") (pin "A26") (pinfunction "B_A26") (pintype "passive"))
    )
    (net (code "63") (name "DATA8") (class "Default")
      (node (ref "X1") (pin "A27") (pinfunction "B_A27") (pintype "passive"))
    )
    (net (code "64") (name "DATA9") (class "Default")
      (node (ref "X1") (pin "A28") (pinfunction "B_A28") (pintype "passive"))
    )
    (net (code "65") (name "DATA10") (class "Default")
      (node (ref "X1") (pin "A29") (pinfunction "B_A29") (pintype "passive"))
    )
    (net (code "66") (name "DATA11") (class "Default")
      (node (ref "X1") (pin "A30") (pinfunction "B_A30") (pintype "passive"))
    )
    (net (code "67") (name "DATA12") (class "Default")
      (node (ref "X1") (pin "B3") (pinfunction "B_B3") (pintype "passive"))
    )
    (net (code "68") (name "DATA13") (class "Default")
      (node (ref "X1") (pin "B4") (pinfunction "B_B4") (pintype "passive"))
    )
    (net (code "69") (name "DATA14") (class "Default")
      (node (ref "X1") (pin "B5") (pinfunction "B_B5") (pintype "passive"))
    )
    (net (code "70") (name "DATA15") (class "Default")
      (node (ref "X1") (pin "B6") (pinfunction "B_B6") (pintype "passive"))
    )
    (net (code "71") (name "GND") (class "Default")
      (node (ref "0000") (pin "10") (pinfunction "10_10") (pintype "passive"))
      (node (ref "0000") (pin "11") (pinfunction "11_11") (pintype "passive"))
      (node (ref "0000") (pin "12") (pinfunction "12_12") (pintype "passive"))
      (node (ref "0000") (pin "13") (pinfunction "13_13") (pintype "passive"))
      (node (ref "0000") (pin "14") (pinfunction "14_14") (pintype "passive"))
      (node (ref "0000") (pin "15") (pinfunction "15_15") (pintype "passive"))
      (node (ref "0000") (pin "16") (pinfunction "16_16") (pintype "passive"))
      (node (ref "0000") (pin "9") (pinfunction "9_9") (pintype "passive"))
      (node (ref "0001") (pin "10") (pinfunction "10_10") (pintype "passive"))
      (node (ref "0001") (pin "11") (pinfunction "11_11") (pintype "passive"))
      (node (ref "0001") (pin "12") (pinfunction "12_12") (pintype "passive"))
      (node (ref "0001") (pin "13") (pinfunction "13_13") (pintype "passive"))
      (node (ref "0001") (pin "14") (pinfunction "14_14") (pintype "passive"))
      (node (ref "0001") (pin "15") (pinfunction "15_15") (pintype "passive"))
      (node (ref "0001") (pin "16") (pinfunction "16_16") (pintype "passive"))
      (node (ref "0001") (pin "9") (pinfunction "9_9") (pintype "passive"))
      (node (ref "0010") (pin "10") (pinfunction "10_10") (pintype "passive"))
      (node (ref "0010") (pin "11") (pinfunction "11_11") (pintype "passive"))
      (node (ref "0010") (pin "12") (pinfunction "12_12") (pintype "passive"))
      (node (ref "0010") (pin "13") (pinfunction "13_13") (pintype "passive"))
      (node (ref "0010") (pin "14") (pinfunction "14_14") (pintype "passive"))
      (node (ref "0010") (pin "15") (pinfunction "15_15") (pintype "passive"))
      (node (ref "0010") (pin "16") (pinfunction "16_16") (pintype "passive"))
      (node (ref "0010") (pin "9") (pinfunction "9_9") (pintype "passive"))
      (node (ref "0011") (pin "10") (pinfunction "10_10") (pintype "passive"))
      (node (ref "0011") (pin "11") (pinfunction "11_11") (pintype "passive"))
      (node (ref "0011") (pin "12") (pinfunction "12_12") (pintype "passive"))
      (node (ref "0011") (pin "13") (pinfunction "13_13") (pintype "passive"))
      (node (ref "0011") (pin "14") (pinfunction "14_14") (pintype "passive"))
      (node (ref "0011") (pin "15") (pinfunction "15_15") (pintype "passive"))
      (node (ref "0011") (pin "16") (pinfunction "16_16") (pintype "passive"))
      (node (ref "0011") (pin "9") (pinfunction "9_9") (pintype "passive"))
      (node (ref "0100") (pin "10") (pinfunction "10_10") (pintype "passive"))
      (node (ref "0100") (pin "11") (pinfunction "11_11") (pintype "passive"))
      (node (ref "0100") (pin "12") (pinfunction "12_12") (pintype "passive"))
      (node (ref "0100") (pin "13") (pinfunction "13_13") (pintype "passive"))
      (node (ref "0100") (pin "14") (pinfunction "14_14") (pintype "passive"))
      (node (ref "0100") (pin "15") (pinfunction "15_15") (pintype "passive"))
      (node (ref "0100") (pin "16") (pinfunction "16_16") (pintype "passive"))
      (node (ref "0100") (pin "9") (pinfunction "9_9") (pintype "passive"))
      (node (ref "0101") (pin "10") (pinfunction "10_10") (pintype "passive"))
      (node (ref "0101") (pin "11") (pinfunction "11_11") (pintype "passive"))
      (node (ref "0101") (pin "12") (pinfunction "12_12") (pintype "passive"))
      (node (ref "0101") (pin "13") (pinfunction "13_13") (pintype "passive"))
      (node (ref "0101") (pin "14") (pinfunction "14_14") (pintype "passive"))
      (node (ref "0101") (pin "15") (pinfunction "15_15") (pintype "passive"))
      (node (ref "0101") (pin "16") (pinfunction "16_16") (pintype "passive"))
      (node (ref "0101") (pin "9") (pinfunction "9_9") (pintype "passive"))
      (node (ref "0110") (pin "10") (pinfunction "10_10") (pintype "passive"))
      (node (ref "0110") (pin "11") (pinfunction "11_11") (pintype "passive"))
      (node (ref "0110") (pin "12") (pinfunction "12_12") (pintype "passive"))
      (node (ref "0110") (pin "13") (pinfunction "13_13") (pintype "passive"))
      (node (ref "0110") (pin "14") (pinfunction "14_14") (pintype "passive"))
      (node (ref "0110") (pin "15") (pinfunction "15_15") (pintype "passive"))
      (node (ref "0110") (pin "16") (pinfunction "16_16") (pintype "passive"))
      (node (ref "0110") (pin "9") (pinfunction "9_9") (pintype "passive"))
      (node (ref "0111") (pin "10") (pinfunction "10_10") (pintype "passive"))
      (node (ref "0111") (pin "11") (pinfunction "11_11") (pintype "passive"))
      (node (ref "0111") (pin "12") (pinfunction "12_12") (pintype "passive"))
      (node (ref "0111") (pin "13") (pinfunction "13_13") (pintype "passive"))
      (node (ref "0111") (pin "14") (pinfunction "14_14") (pintype "passive"))
      (node (ref "0111") (pin "15") (pinfunction "15_15") (pintype "passive"))
      (node (ref "0111") (pin "16") (pinfunction "16_16") (pintype "passive"))
      (node (ref "0111") (pin "9") (pinfunction "9_9") (pintype "passive"))
      (node (ref "1000") (pin "10") (pinfunction "10_10") (pintype "passive"))
      (node (ref "1000") (pin "11") (pinfunction "11_11") (pintype "passive"))
      (node (ref "1000") (pin "12") (pinfunction "12_12") (pintype "passive"))
      (node (ref "1000") (pin "13") (pinfunction "13_13") (pintype "passive"))
      (node (ref "1000") (pin "14") (pinfunction "14_14") (pintype "passive"))
      (node (ref "1000") (pin "15") (pinfunction "15_15") (pintype "passive"))
      (node (ref "1000") (pin "16") (pinfunction "16_16") (pintype "passive"))
      (node (ref "1000") (pin "9") (pinfunction "9_9") (pintype "passive"))
      (node (ref "1001") (pin "10") (pinfunction "10_10") (pintype "passive"))
      (node (ref "1001") (pin "11") (pinfunction "11_11") (pintype "passive"))
      (node (ref "1001") (pin "12") (pinfunction "12_12") (pintype "passive"))
      (node (ref "1001") (pin "13") (pinfunction "13_13") (pintype "passive"))
      (node (ref "1001") (pin "14") (pinfunction "14_14") (pintype "passive"))
      (node (ref "1001") (pin "15") (pinfunction "15_15") (pintype "passive"))
      (node (ref "1001") (pin "16") (pinfunction "16_16") (pintype "passive"))
      (node (ref "1001") (pin "9") (pinfunction "9_9") (pintype "passive"))
      (node (ref "1010") (pin "10") (pinfunction "10_10") (pintype "passive"))
      (node (ref "1010") (pin "11") (pinfunction "11_11") (pintype "passive"))
      (node (ref "1010") (pin "12") (pinfunction "12_12") (pintype "passive"))
      (node (ref "1010") (pin "13") (pinfunction "13_13") (pintype "passive"))
      (node (ref "1010") (pin "14") (pinfunction "14_14") (pintype "passive"))
      (node (ref "1010") (pin "15") (pinfunction "15_15") (pintype "passive"))
      (node (ref "1010") (pin "16") (pinfunction "16_16") (pintype "passive"))
      (node (ref "1010") (pin "9") (pinfunction "9_9") (pintype "passive"))
      (node (ref "1011") (pin "10") (pinfunction "10_10") (pintype "passive"))
      (node (ref "1011") (pin "11") (pinfunction "11_11") (pintype "passive"))
      (node (ref "1011") (pin "12") (pinfunction "12_12") (pintype "passive"))
      (node (ref "1011") (pin "13") (pinfunction "13_13") (pintype "passive"))
      (node (ref "1011") (pin "14") (pinfunction "14_14") (pintype "passive"))
      (node (ref "1011") (pin "15") (pinfunction "15_15") (pintype "passive"))
      (node (ref "1011") (pin "16") (pinfunction "16_16") (pintype "passive"))
      (node (ref "1011") (pin "9") (pinfunction "9_9") (pintype "passive"))
      (node (ref "1100") (pin "10") (pinfunction "10_10") (pintype "passive"))
      (node (ref "1100") (pin "11") (pinfunction "11_11") (pintype "passive"))
      (node (ref "1100") (pin "12") (pinfunction "12_12") (pintype "passive"))
      (node (ref "1100") (pin "13") (pinfunction "13_13") (pintype "passive"))
      (node (ref "1100") (pin "14") (pinfunction "14_14") (pintype "passive"))
      (node (ref "1100") (pin "15") (pinfunction "15_15") (pintype "passive"))
      (node (ref "1100") (pin "16") (pinfunction "16_16") (pintype "passive"))
      (node (ref "1100") (pin "9") (pinfunction "9_9") (pintype "passive"))
      (node (ref "1101") (pin "10") (pinfunction "10_10") (pintype "passive"))
      (node (ref "1101") (pin "11") (pinfunction "11_11") (pintype "passive"))
      (node (ref "1101") (pin "12") (pinfunction "12_12") (pintype "passive"))
      (node (ref "1101") (pin "13") (pinfunction "13_13") (pintype "passive"))
      (node (ref "1101") (pin "14") (pinfunction "14_14") (pintype "passive"))
      (node (ref "1101") (pin "15") (pinfunction "15_15") (pintype "passive"))
      (node (ref "1101") (pin "16") (pinfunction "16_16") (pintype "passive"))
      (node (ref "1101") (pin "9") (pinfunction "9_9") (pintype "passive"))
      (node (ref "1110") (pin "10") (pinfunction "10_10") (pintype "passive"))
      (node (ref "1110") (pin "11") (pinfunction "11_11") (pintype "passive"))
      (node (ref "1110") (pin "12") (pinfunction "12_12") (pintype "passive"))
      (node (ref "1110") (pin "13") (pinfunction "13_13") (pintype "passive"))
      (node (ref "1110") (pin "14") (pinfunction "14_14") (pintype "passive"))
      (node (ref "1110") (pin "15") (pinfunction "15_15") (pintype "passive"))
      (node (ref "1110") (pin "16") (pinfunction "16_16") (pintype "passive"))
      (node (ref "1110") (pin "9") (pinfunction "9_9") (pintype "passive"))
      (node (ref "1111") (pin "10") (pinfunction "10_10") (pintype "passive"))
      (node (ref "1111") (pin "11") (pinfunction "11_11") (pintype "passive"))
      (node (ref "1111") (pin "12") (pinfunction "12_12") (pintype "passive"))
      (node (ref "1111") (pin "13") (pinfunction "13_13") (pintype "passive"))
      (node (ref "1111") (pin "14") (pinfunction "14_14") (pintype "passive"))
      (node (ref "1111") (pin "15") (pinfunction "15_15") (pintype "passive"))
      (node (ref "1111") (pin "16") (pinfunction "16_16") (pintype "passive"))
      (node (ref "1111") (pin "9") (pinfunction "9_9") (pintype "passive"))
      (node (ref "C1") (pin "2") (pinfunction "2_2") (pintype "passive"))
      (node (ref "C10") (pin "2") (pinfunction "2_2") (pintype "passive"))
      (node (ref "C11") (pin "2") (pinfunction "2_2") (pintype "passive"))
      (node (ref "C12") (pin "2") (pinfunction "2_2") (pintype "passive"))
      (node (ref "C13") (pin "2") (pinfunction "2_2") (pintype "passive"))
      (node (ref "C14") (pin "2") (pinfunction "2_2") (pintype "passive"))
      (node (ref "C15") (pin "2") (pinfunction "2_2") (pintype "passive"))
      (node (ref "C16") (pin "2") (pinfunction "2_2") (pintype "passive"))
      (node (ref "C17") (pin "2") (pinfunction "2_2") (pintype "passive"))
      (node (ref "C18") (pin "2") (pinfunction "2_2") (pintype "passive"))
      (node (ref "C19") (pin "2") (pinfunction "2_2") (pintype "passive"))
      (node (ref "C2") (pin "2") (pinfunction "2_2") (pintype "passive"))
      (node (ref "C20") (pin "2") (pinfunction "2_2") (pintype "passive"))
      (node (ref "C21") (pin "2") (pinfunction "2_2") (pintype "passive"))
      (node (ref "C3") (pin "2") (pinfunction "2_2") (pintype "passive"))
      (node (ref "C4") (pin "2") (pinfunction "2_2") (pintype "passive"))
      (node (ref "C5") (pin "2") (pinfunction "2_2") (pintype "passive"))
      (node (ref "C6") (pin "2") (pinfunction "2_2") (pintype "passive"))
      (node (ref "C7") (pin "2") (pinfunction "2_2") (pintype "passive"))
      (node (ref "C8") (pin "2") (pinfunction "2_2") (pintype "passive"))
      (node (ref "C9") (pin "2") (pinfunction "2_2") (pintype "passive"))
      (node (ref "IC4") (pin "2") (pinfunction "A<B_I_2") (pintype "input"))
      (node (ref "IC4") (pin "4") (pinfunction "A>B_I_4") (pintype "input"))
      (node (ref "PWR") (pin "K") (pinfunction "C_K") (pintype "passive"))
      (node (ref "RN1") (pin "1") (pinfunction "1_1") (pintype "passive"))
      (node (ref "V1") (pin "7") (pinfunction "-UB_7") (pintype "power_in"))
      (node (ref "X1") (pin "A1") (pinfunction "B_A1") (pintype "passive"))
      (node (ref "X1") (pin "A32") (pinfunction "B_A32") (pintype "passive"))
      (node (ref "X1") (pin "B1") (pinfunction "B_B1") (pintype "passive"))
      (node (ref "X1") (pin "B32") (pinfunction "B_B32") (pintype "passive"))
      (node (ref "X1") (pin "C1") (pinfunction "B_C1") (pintype "passive"))
      (node (ref "X1") (pin "C32") (pinfunction "B_C32") (pintype "passive"))
    )
    (net (code "72") (name "IN") (class "Default")
      (node (ref "X1") (pin "C26") (pinfunction "B_C26") (pintype "passive"))
    )
    (net (code "73") (name "IO-ADDR0") (class "Default")
      (node (ref "X1") (pin "C7") (pinfunction "B_C7") (pintype "passive"))
    )
    (net (code "74") (name "IO-ADDR1") (class "Default")
      (node (ref "X1") (pin "C8") (pinfunction "B_C8") (pintype "passive"))
    )
    (net (code "75") (name "IO-ADDR2") (class "Default")
      (node (ref "X1") (pin "C9") (pinfunction "B_C9") (pintype "passive"))
    )
    (net (code "76") (name "IO-ADDR3") (class "Default")
      (node (ref "X1") (pin "C10") (pinfunction "B_C10") (pintype "passive"))
    )
    (net (code "77") (name "Net-(IC1A-O)") (class "Default")
      (node (ref "IC1") (pin "10") (pinfunction "I1_10") (pintype "input"))
      (node (ref "IC1") (pin "11") (pinfunction "I2_11") (pintype "input"))
      (node (ref "IC1") (pin "12") (pinfunction "O_12") (pintype "output"))
      (node (ref "IC1") (pin "9") (pinfunction "I0_9") (pintype "input"))
    )
    (net (code "78") (name "Net-(IC1B-O)") (class "Default")
      (node (ref "IC1") (pin "6") (pinfunction "O_6") (pintype "output"))
      (node (ref "IC3") (pin "5") (pinfunction "G2B_5") (pintype "input"))
    )
    (net (code "79") (name "Net-(IC1C-O)") (class "Default")
      (node (ref "IC1") (pin "8") (pinfunction "O_8") (pintype "output"))
      (node (ref "IC2") (pin "4") (pinfunction "G2A_4") (pintype "input"))
      (node (ref "IC3") (pin "4") (pinfunction "G2A_4") (pintype "input"))
    )
    (net (code "80") (name "Net-(IC2A-G1)") (class "Default")
      (node (ref "BRD-SEL") (pin "1") (pinfunction "1_1") (pintype "passive"))
      (node (ref "IC2") (pin "6") (pinfunction "G1_6") (pintype "input"))
      (node (ref "IC3") (pin "6") (pinfunction "G1_6") (pintype "input"))
      (node (ref "IC4") (pin "6") (pinfunction "A=B_O_6") (pintype "output"))
    )
    (net (code "81") (name "Net-(IC4A-A=B_I)") (class "Default")
      (node (ref "IC4") (pin "3") (pinfunction "A=B_I_3") (pintype "input"))
      (node (ref "V1") (pin "13") (pinfunction "W_13") (pintype "output"))
    )
    (net (code "82") (name "Net-(IC4A-B0)") (class "Default")
      (node (ref "IC4") (pin "9") (pinfunction "B0_9") (pintype "input"))
      (node (ref "RN1") (pin "2") (pinfunction "2_2") (pintype "passive"))
      (node (ref "SW1") (pin "8") (pinfunction "8_8") (pintype "passive"))
    )
    (net (code "83") (name "Net-(IC4A-B1)") (class "Default")
      (node (ref "IC4") (pin "11") (pinfunction "B1_11") (pintype "input"))
      (node (ref "RN1") (pin "3") (pinfunction "3_3") (pintype "passive"))
      (node (ref "SW1") (pin "7") (pinfunction "7_7") (pintype "passive"))
    )
    (net (code "84") (name "Net-(IC4A-B2)") (class "Default")
      (node (ref "IC4") (pin "14") (pinfunction "B2_14") (pintype "input"))
      (node (ref "RN1") (pin "4") (pinfunction "4_4") (pintype "passive"))
      (node (ref "SW1") (pin "6") (pinfunction "6_6") (pintype "passive"))
    )
    (net (code "85") (name "Net-(IC4A-B3)") (class "Default")
      (node (ref "IC4") (pin "1") (pinfunction "B3_1") (pintype "input"))
      (node (ref "RN1") (pin "5") (pinfunction "5_5") (pintype "passive"))
      (node (ref "SW1") (pin "5") (pinfunction "5_5") (pintype "passive"))
    )
    (net (code "86") (name "Net-(IC5A-A1)") (class "Default")
      (node (ref "0000") (pin "8") (pinfunction "8_8") (pintype "passive"))
      (node (ref "IC5") (pin "2") (pinfunction "A1_2") (pintype "input"))
      (node (ref "RN2") (pin "9") (pinfunction "9_9") (pintype "passive"))
    )
    (net (code "87") (name "Net-(IC5A-A2)") (class "Default")
      (node (ref "0000") (pin "7") (pinfunction "7_7") (pintype "passive"))
      (node (ref "IC5") (pin "4") (pinfunction "A2_4") (pintype "input"))
      (node (ref "RN2") (pin "8") (pinfunction "8_8") (pintype "passive"))
    )
    (net (code "88") (name "Net-(IC5A-A3)") (class "Default")
      (node (ref "0000") (pin "6") (pinfunction "6_6") (pintype "passive"))
      (node (ref "IC5") (pin "6") (pinfunction "A3_6") (pintype "input"))
      (node (ref "RN2") (pin "7") (pinfunction "7_7") (pintype "passive"))
    )
    (net (code "89") (name "Net-(IC5A-A4)") (class "Default")
      (node (ref "0000") (pin "5") (pinfunction "5_5") (pintype "passive"))
      (node (ref "IC5") (pin "8") (pinfunction "A4_8") (pintype "input"))
      (node (ref "RN2") (pin "6") (pinfunction "6_6") (pintype "passive"))
    )
    (net (code "90") (name "Net-(IC5B-A1)") (class "Default")
      (node (ref "0000") (pin "4") (pinfunction "4_4") (pintype "passive"))
      (node (ref "IC5") (pin "11") (pinfunction "A1_11") (pintype "input"))
      (node (ref "RN2") (pin "5") (pinfunction "5_5") (pintype "passive"))
    )
    (net (code "91") (name "Net-(IC5B-A2)") (class "Default")
      (node (ref "0000") (pin "3") (pinfunction "3_3") (pintype "passive"))
      (node (ref "IC5") (pin "13") (pinfunction "A2_13") (pintype "input"))
      (node (ref "RN2") (pin "4") (pinfunction "4_4") (pintype "passive"))
    )
    (net (code "92") (name "Net-(IC5B-A3)") (class "Default")
      (node (ref "0000") (pin "2") (pinfunction "2_2") (pintype "passive"))
      (node (ref "IC5") (pin "15") (pinfunction "A3_15") (pintype "input"))
      (node (ref "RN2") (pin "3") (pinfunction "3_3") (pintype "passive"))
    )
    (net (code "93") (name "Net-(IC5B-A4)") (class "Default")
      (node (ref "0000") (pin "1") (pinfunction "1_1") (pintype "passive"))
      (node (ref "IC5") (pin "17") (pinfunction "A4_17") (pintype "input"))
      (node (ref "RN2") (pin "2") (pinfunction "2_2") (pintype "passive"))
    )
    (net (code "94") (name "Net-(IC6A-A1)") (class "Default")
      (node (ref "0001") (pin "8") (pinfunction "8_8") (pintype "passive"))
      (node (ref "IC6") (pin "2") (pinfunction "A1_2") (pintype "input"))
      (node (ref "RN3") (pin "9") (pinfunction "9_9") (pintype "passive"))
    )
    (net (code "95") (name "Net-(IC6A-A2)") (class "Default")
      (node (ref "0001") (pin "7") (pinfunction "7_7") (pintype "passive"))
      (node (ref "IC6") (pin "4") (pinfunction "A2_4") (pintype "input"))
      (node (ref "RN3") (pin "8") (pinfunction "8_8") (pintype "passive"))
    )
    (net (code "96") (name "Net-(IC6A-A3)") (class "Default")
      (node (ref "0001") (pin "6") (pinfunction "6_6") (pintype "passive"))
      (node (ref "IC6") (pin "6") (pinfunction "A3_6") (pintype "input"))
      (node (ref "RN3") (pin "7") (pinfunction "7_7") (pintype "passive"))
    )
    (net (code "97") (name "Net-(IC6A-A4)") (class "Default")
      (node (ref "0001") (pin "5") (pinfunction "5_5") (pintype "passive"))
      (node (ref "IC6") (pin "8") (pinfunction "A4_8") (pintype "input"))
      (node (ref "RN3") (pin "6") (pinfunction "6_6") (pintype "passive"))
    )
    (net (code "98") (name "Net-(IC6B-A1)") (class "Default")
      (node (ref "0001") (pin "4") (pinfunction "4_4") (pintype "passive"))
      (node (ref "IC6") (pin "11") (pinfunction "A1_11") (pintype "input"))
      (node (ref "RN3") (pin "5") (pinfunction "5_5") (pintype "passive"))
    )
    (net (code "99") (name "Net-(IC6B-A2)") (class "Default")
      (node (ref "0001") (pin "3") (pinfunction "3_3") (pintype "passive"))
      (node (ref "IC6") (pin "13") (pinfunction "A2_13") (pintype "input"))
      (node (ref "RN3") (pin "4") (pinfunction "4_4") (pintype "passive"))
    )
    (net (code "100") (name "Net-(IC6B-A3)") (class "Default")
      (node (ref "0001") (pin "2") (pinfunction "2_2") (pintype "passive"))
      (node (ref "IC6") (pin "15") (pinfunction "A3_15") (pintype "input"))
      (node (ref "RN3") (pin "3") (pinfunction "3_3") (pintype "passive"))
    )
    (net (code "101") (name "Net-(IC6B-A4)") (class "Default")
      (node (ref "0001") (pin "1") (pinfunction "1_1") (pintype "passive"))
      (node (ref "IC6") (pin "17") (pinfunction "A4_17") (pintype "input"))
      (node (ref "RN3") (pin "2") (pinfunction "2_2") (pintype "passive"))
    )
    (net (code "102") (name "Net-(IC7A-A1)") (class "Default")
      (node (ref "0010") (pin "8") (pinfunction "8_8") (pintype "passive"))
      (node (ref "IC7") (pin "2") (pinfunction "A1_2") (pintype "input"))
      (node (ref "RN4") (pin "9") (pinfunction "9_9") (pintype "passive"))
    )
    (net (code "103") (name "Net-(IC7A-A2)") (class "Default")
      (node (ref "0010") (pin "7") (pinfunction "7_7") (pintype "passive"))
      (node (ref "IC7") (pin "4") (pinfunction "A2_4") (pintype "input"))
      (node (ref "RN4") (pin "8") (pinfunction "8_8") (pintype "passive"))
    )
    (net (code "104") (name "Net-(IC7A-A3)") (class "Default")
      (node (ref "0010") (pin "6") (pinfunction "6_6") (pintype "passive"))
      (node (ref "IC7") (pin "6") (pinfunction "A3_6") (pintype "input"))
      (node (ref "RN4") (pin "7") (pinfunction "7_7") (pintype "passive"))
    )
    (net (code "105") (name "Net-(IC7A-A4)") (class "Default")
      (node (ref "0010") (pin "5") (pinfunction "5_5") (pintype "passive"))
      (node (ref "IC7") (pin "8") (pinfunction "A4_8") (pintype "input"))
      (node (ref "RN4") (pin "6") (pinfunction "6_6") (pintype "passive"))
    )
    (net (code "106") (name "Net-(IC7B-A1)") (class "Default")
      (node (ref "0010") (pin "4") (pinfunction "4_4") (pintype "passive"))
      (node (ref "IC7") (pin "11") (pinfunction "A1_11") (pintype "input"))
      (node (ref "RN4") (pin "5") (pinfunction "5_5") (pintype "passive"))
    )
    (net (code "107") (name "Net-(IC7B-A2)") (class "Default")
      (node (ref "0010") (pin "3") (pinfunction "3_3") (pintype "passive"))
      (node (ref "IC7") (pin "13") (pinfunction "A2_13") (pintype "input"))
      (node (ref "RN4") (pin "4") (pinfunction "4_4") (pintype "passive"))
    )
    (net (code "108") (name "Net-(IC7B-A3)") (class "Default")
      (node (ref "0010") (pin "2") (pinfunction "2_2") (pintype "passive"))
      (node (ref "IC7") (pin "15") (pinfunction "A3_15") (pintype "input"))
      (node (ref "RN4") (pin "3") (pinfunction "3_3") (pintype "passive"))
    )
    (net (code "109") (name "Net-(IC7B-A4)") (class "Default")
      (node (ref "0010") (pin "1") (pinfunction "1_1") (pintype "passive"))
      (node (ref "IC7") (pin "17") (pinfunction "A4_17") (pintype "input"))
      (node (ref "RN4") (pin "2") (pinfunction "2_2") (pintype "passive"))
    )
    (net (code "110") (name "Net-(IC8A-A1)") (class "Default")
      (node (ref "0011") (pin "8") (pinfunction "8_8") (pintype "passive"))
      (node (ref "IC8") (pin "2") (pinfunction "A1_2") (pintype "input"))
      (node (ref "RN5") (pin "9") (pinfunction "9_9") (pintype "passive"))
    )
    (net (code "111") (name "Net-(IC8A-A2)") (class "Default")
      (node (ref "0011") (pin "7") (pinfunction "7_7") (pintype "passive"))
      (node (ref "IC8") (pin "4") (pinfunction "A2_4") (pintype "input"))
      (node (ref "RN5") (pin "8") (pinfunction "8_8") (pintype "passive"))
    )
    (net (code "112") (name "Net-(IC8A-A3)") (class "Default")
      (node (ref "0011") (pin "6") (pinfunction "6_6") (pintype "passive"))
      (node (ref "IC8") (pin "6") (pinfunction "A3_6") (pintype "input"))
      (node (ref "RN5") (pin "7") (pinfunction "7_7") (pintype "passive"))
    )
    (net (code "113") (name "Net-(IC8A-A4)") (class "Default")
      (node (ref "0011") (pin "5") (pinfunction "5_5") (pintype "passive"))
      (node (ref "IC8") (pin "8") (pinfunction "A4_8") (pintype "input"))
      (node (ref "RN5") (pin "6") (pinfunction "6_6") (pintype "passive"))
    )
    (net (code "114") (name "Net-(IC8B-A1)") (class "Default")
      (node (ref "0011") (pin "4") (pinfunction "4_4") (pintype "passive"))
      (node (ref "IC8") (pin "11") (pinfunction "A1_11") (pintype "input"))
      (node (ref "RN5") (pin "5") (pinfunction "5_5") (pintype "passive"))
    )
    (net (code "115") (name "Net-(IC8B-A2)") (class "Default")
      (node (ref "0011") (pin "3") (pinfunction "3_3") (pintype "passive"))
      (node (ref "IC8") (pin "13") (pinfunction "A2_13") (pintype "input"))
      (node (ref "RN5") (pin "4") (pinfunction "4_4") (pintype "passive"))
    )
    (net (code "116") (name "Net-(IC8B-A3)") (class "Default")
      (node (ref "0011") (pin "2") (pinfunction "2_2") (pintype "passive"))
      (node (ref "IC8") (pin "15") (pinfunction "A3_15") (pintype "input"))
      (node (ref "RN5") (pin "3") (pinfunction "3_3") (pintype "passive"))
    )
    (net (code "117") (name "Net-(IC8B-A4)") (class "Default")
      (node (ref "0011") (pin "1") (pinfunction "1_1") (pintype "passive"))
      (node (ref "IC8") (pin "17") (pinfunction "A4_17") (pintype "input"))
      (node (ref "RN5") (pin "2") (pinfunction "2_2") (pintype "passive"))
    )
    (net (code "118") (name "Net-(IC9A-A1)") (class "Default")
      (node (ref "0100") (pin "8") (pinfunction "8_8") (pintype "passive"))
      (node (ref "IC9") (pin "2") (pinfunction "A1_2") (pintype "input"))
      (node (ref "RN6") (pin "9") (pinfunction "9_9") (pintype "passive"))
    )
    (net (code "119") (name "Net-(IC9A-A2)") (class "Default")
      (node (ref "0100") (pin "7") (pinfunction "7_7") (pintype "passive"))
      (node (ref "IC9") (pin "4") (pinfunction "A2_4") (pintype "input"))
      (node (ref "RN6") (pin "8") (pinfunction "8_8") (pintype "passive"))
    )
    (net (code "120") (name "Net-(IC9A-A3)") (class "Default")
      (node (ref "0100") (pin "6") (pinfunction "6_6") (pintype "passive"))
      (node (ref "IC9") (pin "6") (pinfunction "A3_6") (pintype "input"))
      (node (ref "RN6") (pin "7") (pinfunction "7_7") (pintype "passive"))
    )
    (net (code "121") (name "Net-(IC9A-A4)") (class "Default")
      (node (ref "0100") (pin "5") (pinfunction "5_5") (pintype "passive"))
      (node (ref "IC9") (pin "8") (pinfunction "A4_8") (pintype "input"))
      (node (ref "RN6") (pin "6") (pinfunction "6_6") (pintype "passive"))
    )
    (net (code "122") (name "Net-(IC9B-A1)") (class "Default")
      (node (ref "0100") (pin "4") (pinfunction "4_4") (pintype "passive"))
      (node (ref "IC9") (pin "11") (pinfunction "A1_11") (pintype "input"))
      (node (ref "RN6") (pin "5") (pinfunction "5_5") (pintype "passive"))
    )
    (net (code "123") (name "Net-(IC9B-A2)") (class "Default")
      (node (ref "0100") (pin "3") (pinfunction "3_3") (pintype "passive"))
      (node (ref "IC9") (pin "13") (pinfunction "A2_13") (pintype "input"))
      (node (ref "RN6") (pin "4") (pinfunction "4_4") (pintype "passive"))
    )
    (net (code "124") (name "Net-(IC9B-A3)") (class "Default")
      (node (ref "0100") (pin "2") (pinfunction "2_2") (pintype "passive"))
      (node (ref "IC9") (pin "15") (pinfunction "A3_15") (pintype "input"))
      (node (ref "RN6") (pin "3") (pinfunction "3_3") (pintype "passive"))
    )
    (net (code "125") (name "Net-(IC9B-A4)") (class "Default")
      (node (ref "0100") (pin "1") (pinfunction "1_1") (pintype "passive"))
      (node (ref "IC9") (pin "17") (pinfunction "A4_17") (pintype "input"))
      (node (ref "RN6") (pin "2") (pinfunction "2_2") (pintype "passive"))
    )
    (net (code "126") (name "Net-(IC10A-A1)") (class "Default")
      (node (ref "0101") (pin "8") (pinfunction "8_8") (pintype "passive"))
      (node (ref "IC10") (pin "2") (pinfunction "A1_2") (pintype "input"))
      (node (ref "RN7") (pin "9") (pinfunction "9_9") (pintype "passive"))
    )
    (net (code "127") (name "Net-(IC10A-A2)") (class "Default")
      (node (ref "0101") (pin "7") (pinfunction "7_7") (pintype "passive"))
      (node (ref "IC10") (pin "4") (pinfunction "A2_4") (pintype "input"))
      (node (ref "RN7") (pin "8") (pinfunction "8_8") (pintype "passive"))
    )
    (net (code "128") (name "Net-(IC10A-A3)") (class "Default")
      (node (ref "0101") (pin "6") (pinfunction "6_6") (pintype "passive"))
      (node (ref "IC10") (pin "6") (pinfunction "A3_6") (pintype "input"))
      (node (ref "RN7") (pin "7") (pinfunction "7_7") (pintype "passive"))
    )
    (net (code "129") (name "Net-(IC10A-A4)") (class "Default")
      (node (ref "0101") (pin "5") (pinfunction "5_5") (pintype "passive"))
      (node (ref "IC10") (pin "8") (pinfunction "A4_8") (pintype "input"))
      (node (ref "RN7") (pin "6") (pinfunction "6_6") (pintype "passive"))
    )
    (net (code "130") (name "Net-(IC10B-A1)") (class "Default")
      (node (ref "0101") (pin "4") (pinfunction "4_4") (pintype "passive"))
      (node (ref "IC10") (pin "11") (pinfunction "A1_11") (pintype "input"))
      (node (ref "RN7") (pin "5") (pinfunction "5_5") (pintype "passive"))
    )
    (net (code "131") (name "Net-(IC10B-A2)") (class "Default")
      (node (ref "0101") (pin "3") (pinfunction "3_3") (pintype "passive"))
      (node (ref "IC10") (pin "13") (pinfunction "A2_13") (pintype "input"))
      (node (ref "RN7") (pin "4") (pinfunction "4_4") (pintype "passive"))
    )
    (net (code "132") (name "Net-(IC10B-A3)") (class "Default")
      (node (ref "0101") (pin "2") (pinfunction "2_2") (pintype "passive"))
      (node (ref "IC10") (pin "15") (pinfunction "A3_15") (pintype "input"))
      (node (ref "RN7") (pin "3") (pinfunction "3_3") (pintype "passive"))
    )
    (net (code "133") (name "Net-(IC10B-A4)") (class "Default")
      (node (ref "0101") (pin "1") (pinfunction "1_1") (pintype "passive"))
      (node (ref "IC10") (pin "17") (pinfunction "A4_17") (pintype "input"))
      (node (ref "RN7") (pin "2") (pinfunction "2_2") (pintype "passive"))
    )
    (net (code "134") (name "Net-(IC11A-A1)") (class "Default")
      (node (ref "0110") (pin "8") (pinfunction "8_8") (pintype "passive"))
      (node (ref "IC11") (pin "2") (pinfunction "A1_2") (pintype "input"))
      (node (ref "RN8") (pin "9") (pinfunction "9_9") (pintype "passive"))
    )
    (net (code "135") (name "Net-(IC11A-A2)") (class "Default")
      (node (ref "0110") (pin "7") (pinfunction "7_7") (pintype "passive"))
      (node (ref "IC11") (pin "4") (pinfunction "A2_4") (pintype "input"))
      (node (ref "RN8") (pin "8") (pinfunction "8_8") (pintype "passive"))
    )
    (net (code "136") (name "Net-(IC11A-A3)") (class "Default")
      (node (ref "0110") (pin "6") (pinfunction "6_6") (pintype "passive"))
      (node (ref "IC11") (pin "6") (pinfunction "A3_6") (pintype "input"))
      (node (ref "RN8") (pin "7") (pinfunction "7_7") (pintype "passive"))
    )
    (net (code "137") (name "Net-(IC11A-A4)") (class "Default")
      (node (ref "0110") (pin "5") (pinfunction "5_5") (pintype "passive"))
      (node (ref "IC11") (pin "8") (pinfunction "A4_8") (pintype "input"))
      (node (ref "RN8") (pin "6") (pinfunction "6_6") (pintype "passive"))
    )
    (net (code "138") (name "Net-(IC11B-A1)") (class "Default")
      (node (ref "0110") (pin "4") (pinfunction "4_4") (pintype "passive"))
      (node (ref "IC11") (pin "11") (pinfunction "A1_11") (pintype "input"))
      (node (ref "RN8") (pin "5") (pinfunction "5_5") (pintype "passive"))
    )
    (net (code "139") (name "Net-(IC11B-A2)") (class "Default")
      (node (ref "0110") (pin "3") (pinfunction "3_3") (pintype "passive"))
      (node (ref "IC11") (pin "13") (pinfunction "A2_13") (pintype "input"))
      (node (ref "RN8") (pin "4") (pinfunction "4_4") (pintype "passive"))
    )
    (net (code "140") (name "Net-(IC11B-A3)") (class "Default")
      (node (ref "0110") (pin "2") (pinfunction "2_2") (pintype "passive"))
      (node (ref "IC11") (pin "15") (pinfunction "A3_15") (pintype "input"))
      (node (ref "RN8") (pin "3") (pinfunction "3_3") (pintype "passive"))
    )
    (net (code "141") (name "Net-(IC11B-A4)") (class "Default")
      (node (ref "0110") (pin "1") (pinfunction "1_1") (pintype "passive"))
      (node (ref "IC11") (pin "17") (pinfunction "A4_17") (pintype "input"))
      (node (ref "RN8") (pin "2") (pinfunction "2_2") (pintype "passive"))
    )
    (net (code "142") (name "Net-(IC12A-A1)") (class "Default")
      (node (ref "0111") (pin "8") (pinfunction "8_8") (pintype "passive"))
      (node (ref "IC12") (pin "2") (pinfunction "A1_2") (pintype "input"))
      (node (ref "RN9") (pin "9") (pinfunction "9_9") (pintype "passive"))
    )
    (net (code "143") (name "Net-(IC12A-A2)") (class "Default")
      (node (ref "0111") (pin "7") (pinfunction "7_7") (pintype "passive"))
      (node (ref "IC12") (pin "4") (pinfunction "A2_4") (pintype "input"))
      (node (ref "RN9") (pin "8") (pinfunction "8_8") (pintype "passive"))
    )
    (net (code "144") (name "Net-(IC12A-A3)") (class "Default")
      (node (ref "0111") (pin "6") (pinfunction "6_6") (pintype "passive"))
      (node (ref "IC12") (pin "6") (pinfunction "A3_6") (pintype "input"))
      (node (ref "RN9") (pin "7") (pinfunction "7_7") (pintype "passive"))
    )
    (net (code "145") (name "Net-(IC12A-A4)") (class "Default")
      (node (ref "0111") (pin "5") (pinfunction "5_5") (pintype "passive"))
      (node (ref "IC12") (pin "8") (pinfunction "A4_8") (pintype "input"))
      (node (ref "RN9") (pin "6") (pinfunction "6_6") (pintype "passive"))
    )
    (net (code "146") (name "Net-(IC12B-A1)") (class "Default")
      (node (ref "0111") (pin "4") (pinfunction "4_4") (pintype "passive"))
      (node (ref "IC12") (pin "11") (pinfunction "A1_11") (pintype "input"))
      (node (ref "RN9") (pin "5") (pinfunction "5_5") (pintype "passive"))
    )
    (net (code "147") (name "Net-(IC12B-A2)") (class "Default")
      (node (ref "0111") (pin "3") (pinfunction "3_3") (pintype "passive"))
      (node (ref "IC12") (pin "13") (pinfunction "A2_13") (pintype "input"))
      (node (ref "RN9") (pin "4") (pinfunction "4_4") (pintype "passive"))
    )
    (net (code "148") (name "Net-(IC12B-A3)") (class "Default")
      (node (ref "0111") (pin "2") (pinfunction "2_2") (pintype "passive"))
      (node (ref "IC12") (pin "15") (pinfunction "A3_15") (pintype "input"))
      (node (ref "RN9") (pin "3") (pinfunction "3_3") (pintype "passive"))
    )
    (net (code "149") (name "Net-(IC12B-A4)") (class "Default")
      (node (ref "0111") (pin "1") (pinfunction "1_1") (pintype "passive"))
      (node (ref "IC12") (pin "17") (pinfunction "A4_17") (pintype "input"))
      (node (ref "RN9") (pin "2") (pinfunction "2_2") (pintype "passive"))
    )
    (net (code "150") (name "Net-(IC13A-A1)") (class "Default")
      (node (ref "1000") (pin "8") (pinfunction "8_8") (pintype "passive"))
      (node (ref "IC13") (pin "2") (pinfunction "A1_2") (pintype "input"))
      (node (ref "RN10") (pin "9") (pinfunction "9_9") (pintype "passive"))
    )
    (net (code "151") (name "Net-(IC13A-A2)") (class "Default")
      (node (ref "1000") (pin "7") (pinfunction "7_7") (pintype "passive"))
      (node (ref "IC13") (pin "4") (pinfunction "A2_4") (pintype "input"))
      (node (ref "RN10") (pin "8") (pinfunction "8_8") (pintype "passive"))
    )
    (net (code "152") (name "Net-(IC13A-A3)") (class "Default")
      (node (ref "1000") (pin "6") (pinfunction "6_6") (pintype "passive"))
      (node (ref "IC13") (pin "6") (pinfunction "A3_6") (pintype "input"))
      (node (ref "RN10") (pin "7") (pinfunction "7_7") (pintype "passive"))
    )
    (net (code "153") (name "Net-(IC13A-A4)") (class "Default")
      (node (ref "1000") (pin "5") (pinfunction "5_5") (pintype "passive"))
      (node (ref "IC13") (pin "8") (pinfunction "A4_8") (pintype "input"))
      (node (ref "RN10") (pin "6") (pinfunction "6_6") (pintype "passive"))
    )
    (net (code "154") (name "Net-(IC13B-A1)") (class "Default")
      (node (ref "1000") (pin "4") (pinfunction "4_4") (pintype "passive"))
      (node (ref "IC13") (pin "11") (pinfunction "A1_11") (pintype "input"))
      (node (ref "RN10") (pin "5") (pinfunction "5_5") (pintype "passive"))
    )
    (net (code "155") (name "Net-(IC13B-A2)") (class "Default")
      (node (ref "1000") (pin "3") (pinfunction "3_3") (pintype "passive"))
      (node (ref "IC13") (pin "13") (pinfunction "A2_13") (pintype "input"))
      (node (ref "RN10") (pin "4") (pinfunction "4_4") (pintype "passive"))
    )
    (net (code "156") (name "Net-(IC13B-A3)") (class "Default")
      (node (ref "1000") (pin "2") (pinfunction "2_2") (pintype "passive"))
      (node (ref "IC13") (pin "15") (pinfunction "A3_15") (pintype "input"))
      (node (ref "RN10") (pin "3") (pinfunction "3_3") (pintype "passive"))
    )
    (net (code "157") (name "Net-(IC13B-A4)") (class "Default")
      (node (ref "1000") (pin "1") (pinfunction "1_1") (pintype "passive"))
      (node (ref "IC13") (pin "17") (pinfunction "A4_17") (pintype "input"))
      (node (ref "RN10") (pin "2") (pinfunction "2_2") (pintype "passive"))
    )
    (net (code "158") (name "Net-(IC14A-A1)") (class "Default")
      (node (ref "1001") (pin "8") (pinfunction "8_8") (pintype "passive"))
      (node (ref "IC14") (pin "2") (pinfunction "A1_2") (pintype "input"))
      (node (ref "RN11") (pin "9") (pinfunction "9_9") (pintype "passive"))
    )
    (net (code "159") (name "Net-(IC14A-A2)") (class "Default")
      (node (ref "1001") (pin "7") (pinfunction "7_7") (pintype "passive"))
      (node (ref "IC14") (pin "4") (pinfunction "A2_4") (pintype "input"))
      (node (ref "RN11") (pin "8") (pinfunction "8_8") (pintype "passive"))
    )
    (net (code "160") (name "Net-(IC14A-A3)") (class "Default")
      (node (ref "1001") (pin "6") (pinfunction "6_6") (pintype "passive"))
      (node (ref "IC14") (pin "6") (pinfunction "A3_6") (pintype "input"))
      (node (ref "RN11") (pin "7") (pinfunction "7_7") (pintype "passive"))
    )
    (net (code "161") (name "Net-(IC14A-A4)") (class "Default")
      (node (ref "1001") (pin "5") (pinfunction "5_5") (pintype "passive"))
      (node (ref "IC14") (pin "8") (pinfunction "A4_8") (pintype "input"))
      (node (ref "RN11") (pin "6") (pinfunction "6_6") (pintype "passive"))
    )
    (net (code "162") (name "Net-(IC14B-A1)") (class "Default")
      (node (ref "1001") (pin "4") (pinfunction "4_4") (pintype "passive"))
      (node (ref "IC14") (pin "11") (pinfunction "A1_11") (pintype "input"))
      (node (ref "RN11") (pin "5") (pinfunction "5_5") (pintype "passive"))
    )
    (net (code "163") (name "Net-(IC14B-A2)") (class "Default")
      (node (ref "1001") (pin "3") (pinfunction "3_3") (pintype "passive"))
      (node (ref "IC14") (pin "13") (pinfunction "A2_13") (pintype "input"))
      (node (ref "RN11") (pin "4") (pinfunction "4_4") (pintype "passive"))
    )
    (net (code "164") (name "Net-(IC14B-A3)") (class "Default")
      (node (ref "1001") (pin "2") (pinfunction "2_2") (pintype "passive"))
      (node (ref "IC14") (pin "15") (pinfunction "A3_15") (pintype "input"))
      (node (ref "RN11") (pin "3") (pinfunction "3_3") (pintype "passive"))
    )
    (net (code "165") (name "Net-(IC14B-A4)") (class "Default")
      (node (ref "1001") (pin "1") (pinfunction "1_1") (pintype "passive"))
      (node (ref "IC14") (pin "17") (pinfunction "A4_17") (pintype "input"))
      (node (ref "RN11") (pin "2") (pinfunction "2_2") (pintype "passive"))
    )
    (net (code "166") (name "Net-(IC15A-A1)") (class "Default")
      (node (ref "1010") (pin "8") (pinfunction "8_8") (pintype "passive"))
      (node (ref "IC15") (pin "2") (pinfunction "A1_2") (pintype "input"))
      (node (ref "RN12") (pin "9") (pinfunction "9_9") (pintype "passive"))
    )
    (net (code "167") (name "Net-(IC15A-A2)") (class "Default")
      (node (ref "1010") (pin "7") (pinfunction "7_7") (pintype "passive"))
      (node (ref "IC15") (pin "4") (pinfunction "A2_4") (pintype "input"))
      (node (ref "RN12") (pin "8") (pinfunction "8_8") (pintype "passive"))
    )
    (net (code "168") (name "Net-(IC15A-A3)") (class "Default")
      (node (ref "1010") (pin "6") (pinfunction "6_6") (pintype "passive"))
      (node (ref "IC15") (pin "6") (pinfunction "A3_6") (pintype "input"))
      (node (ref "RN12") (pin "7") (pinfunction "7_7") (pintype "passive"))
    )
    (net (code "169") (name "Net-(IC15A-A4)") (class "Default")
      (node (ref "1010") (pin "5") (pinfunction "5_5") (pintype "passive"))
      (node (ref "IC15") (pin "8") (pinfunction "A4_8") (pintype "input"))
      (node (ref "RN12") (pin "6") (pinfunction "6_6") (pintype "passive"))
    )
    (net (code "170") (name "Net-(IC15B-A1)") (class "Default")
      (node (ref "1010") (pin "4") (pinfunction "4_4") (pintype "passive"))
      (node (ref "IC15") (pin "11") (pinfunction "A1_11") (pintype "input"))
      (node (ref "RN12") (pin "5") (pinfunction "5_5") (pintype "passive"))
    )
    (net (code "171") (name "Net-(IC15B-A2)") (class "Default")
      (node (ref "1010") (pin "3") (pinfunction "3_3") (pintype "passive"))
      (node (ref "IC15") (pin "13") (pinfunction "A2_13") (pintype "input"))
      (node (ref "RN12") (pin "4") (pinfunction "4_4") (pintype "passive"))
    )
    (net (code "172") (name "Net-(IC15B-A3)") (class "Default")
      (node (ref "1010") (pin "2") (pinfunction "2_2") (pintype "passive"))
      (node (ref "IC15") (pin "15") (pinfunction "A3_15") (pintype "input"))
      (node (ref "RN12") (pin "3") (pinfunction "3_3") (pintype "passive"))
    )
    (net (code "173") (name "Net-(IC15B-A4)") (class "Default")
      (node (ref "1010") (pin "1") (pinfunction "1_1") (pintype "passive"))
      (node (ref "IC15") (pin "17") (pinfunction "A4_17") (pintype "input"))
      (node (ref "RN12") (pin "2") (pinfunction "2_2") (pintype "passive"))
    )
    (net (code "174") (name "Net-(IC16A-A1)") (class "Default")
      (node (ref "1011") (pin "8") (pinfunction "8_8") (pintype "passive"))
      (node (ref "IC16") (pin "2") (pinfunction "A1_2") (pintype "input"))
      (node (ref "RN13") (pin "9") (pinfunction "9_9") (pintype "passive"))
    )
    (net (code "175") (name "Net-(IC16A-A2)") (class "Default")
      (node (ref "1011") (pin "7") (pinfunction "7_7") (pintype "passive"))
      (node (ref "IC16") (pin "4") (pinfunction "A2_4") (pintype "input"))
      (node (ref "RN13") (pin "8") (pinfunction "8_8") (pintype "passive"))
    )
    (net (code "176") (name "Net-(IC16A-A3)") (class "Default")
      (node (ref "1011") (pin "6") (pinfunction "6_6") (pintype "passive"))
      (node (ref "IC16") (pin "6") (pinfunction "A3_6") (pintype "input"))
      (node (ref "RN13") (pin "7") (pinfunction "7_7") (pintype "passive"))
    )
    (net (code "177") (name "Net-(IC16A-A4)") (class "Default")
      (node (ref "1011") (pin "5") (pinfunction "5_5") (pintype "passive"))
      (node (ref "IC16") (pin "8") (pinfunction "A4_8") (pintype "input"))
      (node (ref "RN13") (pin "6") (pinfunction "6_6") (pintype "passive"))
    )
    (net (code "178") (name "Net-(IC16B-A1)") (class "Default")
      (node (ref "1011") (pin "4") (pinfunction "4_4") (pintype "passive"))
      (node (ref "IC16") (pin "11") (pinfunction "A1_11") (pintype "input"))
      (node (ref "RN13") (pin "5") (pinfunction "5_5") (pintype "passive"))
    )
    (net (code "179") (name "Net-(IC16B-A2)") (class "Default")
      (node (ref "1011") (pin "3") (pinfunction "3_3") (pintype "passive"))
      (node (ref "IC16") (pin "13") (pinfunction "A2_13") (pintype "input"))
      (node (ref "RN13") (pin "4") (pinfunction "4_4") (pintype "passive"))
    )
    (net (code "180") (name "Net-(IC16B-A3)") (class "Default")
      (node (ref "1011") (pin "2") (pinfunction "2_2") (pintype "passive"))
      (node (ref "IC16") (pin "15") (pinfunction "A3_15") (pintype "input"))
      (node (ref "RN13") (pin "3") (pinfunction "3_3") (pintype "passive"))
    )
    (net (code "181") (name "Net-(IC16B-A4)") (class "Default")
      (node (ref "1011") (pin "1") (pinfunction "1_1") (pintype "passive"))
      (node (ref "IC16") (pin "17") (pinfunction "A4_17") (pintype "input"))
      (node (ref "RN13") (pin "2") (pinfunction "2_2") (pintype "passive"))
    )
    (net (code "182") (name "Net-(IC17A-A1)") (class "Default")
      (node (ref "1100") (pin "8") (pinfunction "8_8") (pintype "passive"))
      (node (ref "IC17") (pin "2") (pinfunction "A1_2") (pintype "input"))
      (node (ref "RN14") (pin "9") (pinfunction "9_9") (pintype "passive"))
    )
    (net (code "183") (name "Net-(IC17A-A2)") (class "Default")
      (node (ref "1100") (pin "7") (pinfunction "7_7") (pintype "passive"))
      (node (ref "IC17") (pin "4") (pinfunction "A2_4") (pintype "input"))
      (node (ref "RN14") (pin "8") (pinfunction "8_8") (pintype "passive"))
    )
    (net (code "184") (name "Net-(IC17A-A3)") (class "Default")
      (node (ref "1100") (pin "6") (pinfunction "6_6") (pintype "passive"))
      (node (ref "IC17") (pin "6") (pinfunction "A3_6") (pintype "input"))
      (node (ref "RN14") (pin "7") (pinfunction "7_7") (pintype "passive"))
    )
    (net (code "185") (name "Net-(IC17A-A4)") (class "Default")
      (node (ref "1100") (pin "5") (pinfunction "5_5") (pintype "passive"))
      (node (ref "IC17") (pin "8") (pinfunction "A4_8") (pintype "input"))
      (node (ref "RN14") (pin "6") (pinfunction "6_6") (pintype "passive"))
    )
    (net (code "186") (name "Net-(IC17B-A1)") (class "Default")
      (node (ref "1100") (pin "4") (pinfunction "4_4") (pintype "passive"))
      (node (ref "IC17") (pin "11") (pinfunction "A1_11") (pintype "input"))
      (node (ref "RN14") (pin "5") (pinfunction "5_5") (pintype "passive"))
    )
    (net (code "187") (name "Net-(IC17B-A2)") (class "Default")
      (node (ref "1100") (pin "3") (pinfunction "3_3") (pintype "passive"))
      (node (ref "IC17") (pin "13") (pinfunction "A2_13") (pintype "input"))
      (node (ref "RN14") (pin "4") (pinfunction "4_4") (pintype "passive"))
    )
    (net (code "188") (name "Net-(IC17B-A3)") (class "Default")
      (node (ref "1100") (pin "2") (pinfunction "2_2") (pintype "passive"))
      (node (ref "IC17") (pin "15") (pinfunction "A3_15") (pintype "input"))
      (node (ref "RN14") (pin "3") (pinfunction "3_3") (pintype "passive"))
    )
    (net (code "189") (name "Net-(IC17B-A4)") (class "Default")
      (node (ref "1100") (pin "1") (pinfunction "1_1") (pintype "passive"))
      (node (ref "IC17") (pin "17") (pinfunction "A4_17") (pintype "input"))
      (node (ref "RN14") (pin "2") (pinfunction "2_2") (pintype "passive"))
    )
    (net (code "190") (name "Net-(IC18A-A1)") (class "Default")
      (node (ref "1101") (pin "8") (pinfunction "8_8") (pintype "passive"))
      (node (ref "IC18") (pin "2") (pinfunction "A1_2") (pintype "input"))
      (node (ref "RN15") (pin "9") (pinfunction "9_9") (pintype "passive"))
    )
    (net (code "191") (name "Net-(IC18A-A2)") (class "Default")
      (node (ref "1101") (pin "7") (pinfunction "7_7") (pintype "passive"))
      (node (ref "IC18") (pin "4") (pinfunction "A2_4") (pintype "input"))
      (node (ref "RN15") (pin "8") (pinfunction "8_8") (pintype "passive"))
    )
    (net (code "192") (name "Net-(IC18A-A3)") (class "Default")
      (node (ref "1101") (pin "6") (pinfunction "6_6") (pintype "passive"))
      (node (ref "IC18") (pin "6") (pinfunction "A3_6") (pintype "input"))
      (node (ref "RN15") (pin "7") (pinfunction "7_7") (pintype "passive"))
    )
    (net (code "193") (name "Net-(IC18A-A4)") (class "Default")
      (node (ref "1101") (pin "5") (pinfunction "5_5") (pintype "passive"))
      (node (ref "IC18") (pin "8") (pinfunction "A4_8") (pintype "input"))
      (node (ref "RN15") (pin "6") (pinfunction "6_6") (pintype "passive"))
    )
    (net (code "194") (name "Net-(IC18B-A1)") (class "Default")
      (node (ref "1101") (pin "4") (pinfunction "4_4") (pintype "passive"))
      (node (ref "IC18") (pin "11") (pinfunction "A1_11") (pintype "input"))
      (node (ref "RN15") (pin "5") (pinfunction "5_5") (pintype "passive"))
    )
    (net (code "195") (name "Net-(IC18B-A2)") (class "Default")
      (node (ref "1101") (pin "3") (pinfunction "3_3") (pintype "passive"))
      (node (ref "IC18") (pin "13") (pinfunction "A2_13") (pintype "input"))
      (node (ref "RN15") (pin "4") (pinfunction "4_4") (pintype "passive"))
    )
    (net (code "196") (name "Net-(IC18B-A3)") (class "Default")
      (node (ref "1101") (pin "2") (pinfunction "2_2") (pintype "passive"))
      (node (ref "IC18") (pin "15") (pinfunction "A3_15") (pintype "input"))
      (node (ref "RN15") (pin "3") (pinfunction "3_3") (pintype "passive"))
    )
    (net (code "197") (name "Net-(IC18B-A4)") (class "Default")
      (node (ref "1101") (pin "1") (pinfunction "1_1") (pintype "passive"))
      (node (ref "IC18") (pin "17") (pinfunction "A4_17") (pintype "input"))
      (node (ref "RN15") (pin "2") (pinfunction "2_2") (pintype "passive"))
    )
    (net (code "198") (name "Net-(IC19A-A1)") (class "Default")
      (node (ref "1110") (pin "8") (pinfunction "8_8") (pintype "passive"))
      (node (ref "IC19") (pin "2") (pinfunction "A1_2") (pintype "input"))
      (node (ref "RN16") (pin "9") (pinfunction "9_9") (pintype "passive"))
    )
    (net (code "199") (name "Net-(IC19A-A2)") (class "Default")
      (node (ref "1110") (pin "7") (pinfunction "7_7") (pintype "passive"))
      (node (ref "IC19") (pin "4") (pinfunction "A2_4") (pintype "input"))
      (node (ref "RN16") (pin "8") (pinfunction "8_8") (pintype "passive"))
    )
    (net (code "200") (name "Net-(IC19A-A3)") (class "Default")
      (node (ref "1110") (pin "6") (pinfunction "6_6") (pintype "passive"))
      (node (ref "IC19") (pin "6") (pinfunction "A3_6") (pintype "input"))
      (node (ref "RN16") (pin "7") (pinfunction "7_7") (pintype "passive"))
    )
    (net (code "201") (name "Net-(IC19A-A4)") (class "Default")
      (node (ref "1110") (pin "5") (pinfunction "5_5") (pintype "passive"))
      (node (ref "IC19") (pin "8") (pinfunction "A4_8") (pintype "input"))
      (node (ref "RN16") (pin "6") (pinfunction "6_6") (pintype "passive"))
    )
    (net (code "202") (name "Net-(IC19B-A1)") (class "Default")
      (node (ref "1110") (pin "4") (pinfunction "4_4") (pintype "passive"))
      (node (ref "IC19") (pin "11") (pinfunction "A1_11") (pintype "input"))
      (node (ref "RN16") (pin "5") (pinfunction "5_5") (pintype "passive"))
    )
    (net (code "203") (name "Net-(IC19B-A2)") (class "Default")
      (node (ref "1110") (pin "3") (pinfunction "3_3") (pintype "passive"))
      (node (ref "IC19") (pin "13") (pinfunction "A2_13") (pintype "input"))
      (node (ref "RN16") (pin "4") (pinfunction "4_4") (pintype "passive"))
    )
    (net (code "204") (name "Net-(IC19B-A3)") (class "Default")
      (node (ref "1110") (pin "2") (pinfunction "2_2") (pintype "passive"))
      (node (ref "IC19") (pin "15") (pinfunction "A3_15") (pintype "input"))
      (node (ref "RN16") (pin "3") (pinfunction "3_3") (pintype "passive"))
    )
    (net (code "205") (name "Net-(IC19B-A4)") (class "Default")
      (node (ref "1110") (pin "1") (pinfunction "1_1") (pintype "passive"))
      (node (ref "IC19") (pin "17") (pinfunction "A4_17") (pintype "input"))
      (node (ref "RN16") (pin "2") (pinfunction "2_2") (pintype "passive"))
    )
    (net (code "206") (name "Net-(IC20A-A1)") (class "Default")
      (node (ref "1111") (pin "8") (pinfunction "8_8") (pintype "passive"))
      (node (ref "IC20") (pin "2") (pinfunction "A1_2") (pintype "input"))
      (node (ref "RN17") (pin "9") (pinfunction "9_9") (pintype "passive"))
    )
    (net (code "207") (name "Net-(IC20A-A2)") (class "Default")
      (node (ref "1111") (pin "7") (pinfunction "7_7") (pintype "passive"))
      (node (ref "IC20") (pin "4") (pinfunction "A2_4") (pintype "input"))
      (node (ref "RN17") (pin "8") (pinfunction "8_8") (pintype "passive"))
    )
    (net (code "208") (name "Net-(IC20A-A3)") (class "Default")
      (node (ref "1111") (pin "6") (pinfunction "6_6") (pintype "passive"))
      (node (ref "IC20") (pin "6") (pinfunction "A3_6") (pintype "input"))
      (node (ref "RN17") (pin "7") (pinfunction "7_7") (pintype "passive"))
    )
    (net (code "209") (name "Net-(IC20A-A4)") (class "Default")
      (node (ref "1111") (pin "5") (pinfunction "5_5") (pintype "passive"))
      (node (ref "IC20") (pin "8") (pinfunction "A4_8") (pintype "input"))
      (node (ref "RN17") (pin "6") (pinfunction "6_6") (pintype "passive"))
    )
    (net (code "210") (name "Net-(IC20B-A1)") (class "Default")
      (node (ref "1111") (pin "4") (pinfunction "4_4") (pintype "passive"))
      (node (ref "IC20") (pin "11") (pinfunction "A1_11") (pintype "input"))
      (node (ref "RN17") (pin "5") (pinfunction "5_5") (pintype "passive"))
    )
    (net (code "211") (name "Net-(IC20B-A2)") (class "Default")
      (node (ref "1111") (pin "3") (pinfunction "3_3") (pintype "passive"))
      (node (ref "IC20") (pin "13") (pinfunction "A2_13") (pintype "input"))
      (node (ref "RN17") (pin "4") (pinfunction "4_4") (pintype "passive"))
    )
    (net (code "212") (name "Net-(IC20B-A3)") (class "Default")
      (node (ref "1111") (pin "2") (pinfunction "2_2") (pintype "passive"))
      (node (ref "IC20") (pin "15") (pinfunction "A3_15") (pintype "input"))
      (node (ref "RN17") (pin "3") (pinfunction "3_3") (pintype "passive"))
    )
    (net (code "213") (name "Net-(IC20B-A4)") (class "Default")
      (node (ref "1111") (pin "1") (pinfunction "1_1") (pintype "passive"))
      (node (ref "IC20") (pin "17") (pinfunction "A4_17") (pintype "input"))
      (node (ref "RN17") (pin "2") (pinfunction "2_2") (pintype "passive"))
    )
    (net (code "214") (name "Net-(PWR-PadA)") (class "Default")
      (node (ref "PWR") (pin "A") (pinfunction "A_A") (pintype "passive"))
      (node (ref "R17") (pin "1") (pinfunction "1_1") (pintype "passive"))
    )
    (net (code "215") (name "Net-(R1-Pad2)") (class "Default")
      (node (ref "R1") (pin "2") (pinfunction "2_2") (pintype "passive"))
      (node (ref "RD0") (pin "A") (pinfunction "A_A") (pintype "passive"))
    )
    (net (code "216") (name "Net-(R2-Pad2)") (class "Default")
      (node (ref "R2") (pin "2") (pinfunction "2_2") (pintype "passive"))
      (node (ref "RD1") (pin "A") (pinfunction "A_A") (pintype "passive"))
    )
    (net (code "217") (name "Net-(R3-Pad2)") (class "Default")
      (node (ref "R3") (pin "2") (pinfunction "2_2") (pintype "passive"))
      (node (ref "RD2") (pin "A") (pinfunction "A_A") (pintype "passive"))
    )
    (net (code "218") (name "Net-(R4-Pad2)") (class "Default")
      (node (ref "R4") (pin "2") (pinfunction "2_2") (pintype "passive"))
      (node (ref "RD3") (pin "A") (pinfunction "A_A") (pintype "passive"))
    )
    (net (code "219") (name "Net-(R5-Pad2)") (class "Default")
      (node (ref "R5") (pin "2") (pinfunction "2_2") (pintype "passive"))
      (node (ref "RD4") (pin "A") (pinfunction "A_A") (pintype "passive"))
    )
    (net (code "220") (name "Net-(R6-Pad2)") (class "Default")
      (node (ref "R6") (pin "2") (pinfunction "2_2") (pintype "passive"))
      (node (ref "RD5") (pin "A") (pinfunction "A_A") (pintype "passive"))
    )
    (net (code "221") (name "Net-(R7-Pad2)") (class "Default")
      (node (ref "R7") (pin "2") (pinfunction "2_2") (pintype "passive"))
      (node (ref "RD6") (pin "A") (pinfunction "A_A") (pintype "passive"))
    )
    (net (code "222") (name "Net-(R8-Pad2)") (class "Default")
      (node (ref "R8") (pin "2") (pinfunction "2_2") (pintype "passive"))
      (node (ref "RD7") (pin "A") (pinfunction "A_A") (pintype "passive"))
    )
    (net (code "223") (name "Net-(R9-Pad2)") (class "Default")
      (node (ref "R9") (pin "2") (pinfunction "2_2") (pintype "passive"))
      (node (ref "RD8") (pin "A") (pinfunction "A_A") (pintype "passive"))
    )
    (net (code "224") (name "Net-(R10-Pad2)") (class "Default")
      (node (ref "R10") (pin "2") (pinfunction "2_2") (pintype "passive"))
      (node (ref "RD9") (pin "A") (pinfunction "A_A") (pintype "passive"))
    )
    (net (code "225") (name "Net-(R11-Pad2)") (class "Default")
      (node (ref "R11") (pin "2") (pinfunction "2_2") (pintype "passive"))
      (node (ref "RD10") (pin "A") (pinfunction "A_A") (pintype "passive"))
    )
    (net (code "226") (name "Net-(R12-Pad2)") (class "Default")
      (node (ref "R12") (pin "2") (pinfunction "2_2") (pintype "passive"))
      (node (ref "RD11") (pin "A") (pinfunction "A_A") (pintype "passive"))
    )
    (net (code "227") (name "Net-(R13-Pad2)") (class "Default")
      (node (ref "R13") (pin "2") (pinfunction "2_2") (pintype "passive"))
      (node (ref "RD12") (pin "A") (pinfunction "A_A") (pintype "passive"))
    )
    (net (code "228") (name "Net-(R14-Pad2)") (class "Default")
      (node (ref "R14") (pin "2") (pinfunction "2_2") (pintype "passive"))
      (node (ref "RD13") (pin "A") (pinfunction "A_A") (pintype "passive"))
    )
    (net (code "229") (name "Net-(R15-Pad2)") (class "Default")
      (node (ref "R15") (pin "2") (pinfunction "2_2") (pintype "passive"))
      (node (ref "RD14") (pin "A") (pinfunction "A_A") (pintype "passive"))
    )
    (net (code "230") (name "Net-(R16-Pad2)") (class "Default")
      (node (ref "R16") (pin "2") (pinfunction "2_2") (pintype "passive"))
      (node (ref "RD15") (pin "A") (pinfunction "A_A") (pintype "passive"))
    )
    (net (code "231") (name "OUT") (class "Default")
      (node (ref "X1") (pin "C27") (pinfunction "B_C27") (pintype "passive"))
    )
    (net (code "232") (name "REG-LD-ID0") (class "Default")
      (node (ref "X1") (pin "B13") (pinfunction "B_B13") (pintype "passive"))
    )
    (net (code "233") (name "REG-LD-ID1") (class "Default")
      (node (ref "X1") (pin "B14") (pinfunction "B_B14") (pintype "passive"))
    )
    (net (code "234") (name "REG-LD-ID2") (class "Default")
      (node (ref "X1") (pin "B15") (pinfunction "B_B15") (pintype "passive"))
    )
    (net (code "235") (name "REG-LD-ID3") (class "Default")
      (node (ref "X1") (pin "B16") (pinfunction "B_B16") (pintype "passive"))
    )
    (net (code "236") (name "REG-RD-ID0") (class "Default")
      (node (ref "X1") (pin "B9") (pinfunction "B_B9") (pintype "passive"))
    )
    (net (code "237") (name "REG-RD-ID1") (class "Default")
      (node (ref "X1") (pin "B10") (pinfunction "B_B10") (pintype "passive"))
    )
    (net (code "238") (name "REG-RD-ID2") (class "Default")
      (node (ref "X1") (pin "B11") (pinfunction "B_B11") (pintype "passive"))
    )
    (net (code "239") (name "REG-RD-ID3") (class "Default")
      (node (ref "X1") (pin "B12") (pinfunction "B_B12") (pintype "passive"))
    )
    (net (code "240") (name "SW0") (class "Default")
      (node (ref "IC2") (pin "15") (pinfunction "Y0_15") (pintype "output"))
      (node (ref "IC5") (pin "1") (pinfunction "G_1") (pintype "input"))
      (node (ref "IC5") (pin "19") (pinfunction "G_19") (pintype "input"))
      (node (ref "RD0") (pin "K") (pinfunction "C_K") (pintype "passive"))
    )
    (net (code "241") (name "SW1") (class "Default")
      (node (ref "IC2") (pin "14") (pinfunction "Y1_14") (pintype "output"))
      (node (ref "IC6") (pin "1") (pinfunction "G_1") (pintype "input"))
      (node (ref "IC6") (pin "19") (pinfunction "G_19") (pintype "input"))
      (node (ref "RD1") (pin "K") (pinfunction "C_K") (pintype "passive"))
    )
    (net (code "242") (name "SW2") (class "Default")
      (node (ref "IC2") (pin "13") (pinfunction "Y2_13") (pintype "output"))
      (node (ref "IC7") (pin "1") (pinfunction "G_1") (pintype "input"))
      (node (ref "IC7") (pin "19") (pinfunction "G_19") (pintype "input"))
      (node (ref "RD2") (pin "K") (pinfunction "C_K") (pintype "passive"))
    )
    (net (code "243") (name "SW3") (class "Default")
      (node (ref "IC2") (pin "12") (pinfunction "Y3_12") (pintype "output"))
      (node (ref "IC8") (pin "1") (pinfunction "G_1") (pintype "input"))
      (node (ref "IC8") (pin "19") (pinfunction "G_19") (pintype "input"))
      (node (ref "RD3") (pin "K") (pinfunction "C_K") (pintype "passive"))
    )
    (net (code "244") (name "SW4") (class "Default")
      (node (ref "IC2") (pin "11") (pinfunction "Y4_11") (pintype "output"))
      (node (ref "IC9") (pin "1") (pinfunction "G_1") (pintype "input"))
      (node (ref "IC9") (pin "19") (pinfunction "G_19") (pintype "input"))
      (node (ref "RD4") (pin "K") (pinfunction "C_K") (pintype "passive"))
    )
    (net (code "245") (name "SW5") (class "Default")
      (node (ref "IC10") (pin "1") (pinfunction "G_1") (pintype "input"))
      (node (ref "IC10") (pin "19") (pinfunction "G_19") (pintype "input"))
      (node (ref "IC2") (pin "10") (pinfunction "Y5_10") (pintype "output"))
      (node (ref "RD5") (pin "K") (pinfunction "C_K") (pintype "passive"))
    )
    (net (code "246") (name "SW6") (class "Default")
      (node (ref "IC11") (pin "1") (pinfunction "G_1") (pintype "input"))
      (node (ref "IC11") (pin "19") (pinfunction "G_19") (pintype "input"))
      (node (ref "IC2") (pin "9") (pinfunction "Y6_9") (pintype "output"))
      (node (ref "RD6") (pin "K") (pinfunction "C_K") (pintype "passive"))
    )
    (net (code "247") (name "SW7") (class "Default")
      (node (ref "IC12") (pin "1") (pinfunction "G_1") (pintype "input"))
      (node (ref "IC12") (pin "19") (pinfunction "G_19") (pintype "input"))
      (node (ref "IC2") (pin "7") (pinfunction "Y7_7") (pintype "output"))
      (node (ref "RD7") (pin "K") (pinfunction "C_K") (pintype "passive"))
    )
    (net (code "248") (name "SW8") (class "Default")
      (node (ref "IC13") (pin "1") (pinfunction "G_1") (pintype "input"))
      (node (ref "IC13") (pin "19") (pinfunction "G_19") (pintype "input"))
      (node (ref "IC3") (pin "15") (pinfunction "Y0_15") (pintype "output"))
      (node (ref "RD8") (pin "K") (pinfunction "C_K") (pintype "passive"))
    )
    (net (code "249") (name "SW9") (class "Default")
      (node (ref "IC14") (pin "1") (pinfunction "G_1") (pintype "input"))
      (node (ref "IC14") (pin "19") (pinfunction "G_19") (pintype "input"))
      (node (ref "IC3") (pin "14") (pinfunction "Y1_14") (pintype "output"))
      (node (ref "RD9") (pin "K") (pinfunction "C_K") (pintype "passive"))
    )
    (net (code "250") (name "SW10") (class "Default")
      (node (ref "IC15") (pin "1") (pinfunction "G_1") (pintype "input"))
      (node (ref "IC15") (pin "19") (pinfunction "G_19") (pintype "input"))
      (node (ref "IC3") (pin "13") (pinfunction "Y2_13") (pintype "output"))
      (node (ref "RD10") (pin "K") (pinfunction "C_K") (pintype "passive"))
    )
    (net (code "251") (name "SW11") (class "Default")
      (node (ref "IC16") (pin "1") (pinfunction "G_1") (pintype "input"))
      (node (ref "IC16") (pin "19") (pinfunction "G_19") (pintype "input"))
      (node (ref "IC3") (pin "12") (pinfunction "Y3_12") (pintype "output"))
      (node (ref "RD11") (pin "K") (pinfunction "C_K") (pintype "passive"))
    )
    (net (code "252") (name "SW12") (class "Default")
      (node (ref "IC17") (pin "1") (pinfunction "G_1") (pintype "input"))
      (node (ref "IC17") (pin "19") (pinfunction "G_19") (pintype "input"))
      (node (ref "IC3") (pin "11") (pinfunction "Y4_11") (pintype "output"))
      (node (ref "RD12") (pin "K") (pinfunction "C_K") (pintype "passive"))
    )
    (net (code "253") (name "SW13") (class "Default")
      (node (ref "IC18") (pin "1") (pinfunction "G_1") (pintype "input"))
      (node (ref "IC18") (pin "19") (pinfunction "G_19") (pintype "input"))
      (node (ref "IC3") (pin "10") (pinfunction "Y5_10") (pintype "output"))
      (node (ref "RD13") (pin "K") (pinfunction "C_K") (pintype "passive"))
    )
    (net (code "254") (name "SW14") (class "Default")
      (node (ref "IC19") (pin "1") (pinfunction "G_1") (pintype "input"))
      (node (ref "IC19") (pin "19") (pinfunction "G_19") (pintype "input"))
      (node (ref "IC3") (pin "9") (pinfunction "Y6_9") (pintype "output"))
      (node (ref "RD14") (pin "K") (pinfunction "C_K") (pintype "passive"))
    )
    (net (code "255") (name "SW15") (class "Default")
      (node (ref "IC20") (pin "1") (pinfunction "G_1") (pintype "input"))
      (node (ref "IC20") (pin "19") (pinfunction "G_19") (pintype "input"))
      (node (ref "IC3") (pin "7") (pinfunction "Y7_7") (pintype "output"))
      (node (ref "RD15") (pin "K") (pinfunction "C_K") (pintype "passive"))
    )
    (net (code "256") (name "VCC") (class "Default")
      (node (ref "C1") (pin "1") (pinfunction "1_1") (pintype "passive"))
      (node (ref "C10") (pin "1") (pinfunction "1_1") (pintype "passive"))
      (node (ref "C11") (pin "1") (pinfunction "1_1") (pintype "passive"))
      (node (ref "C12") (pin "1") (pinfunction "1_1") (pintype "passive"))
      (node (ref "C13") (pin "1") (pinfunction "1_1") (pintype "passive"))
      (node (ref "C14") (pin "1") (pinfunction "1_1") (pintype "passive"))
      (node (ref "C15") (pin "1") (pinfunction "1_1") (pintype "passive"))
      (node (ref "C16") (pin "1") (pinfunction "1_1") (pintype "passive"))
      (node (ref "C17") (pin "1") (pinfunction "1_1") (pintype "passive"))
      (node (ref "C18") (pin "1") (pinfunction "1_1") (pintype "passive"))
      (node (ref "C19") (pin "1") (pinfunction "1_1") (pintype "passive"))
      (node (ref "C2") (pin "1") (pinfunction "1_1") (pintype "passive"))
      (node (ref "C20") (pin "1") (pinfunction "1_1") (pintype "passive"))
      (node (ref "C21") (pin "1") (pinfunction "1_1") (pintype "passive"))
      (node (ref "C3") (pin "1") (pinfunction "1_1") (pintype "passive"))
      (node (ref "C4") (pin "1") (pinfunction "1_1") (pintype "passive"))
      (node (ref "C5") (pin "1") (pinfunction "1_1") (pintype "passive"))
      (node (ref "C6") (pin "1") (pinfunction "1_1") (pintype "passive"))
      (node (ref "C7") (pin "1") (pinfunction "1_1") (pintype "passive"))
      (node (ref "C8") (pin "1") (pinfunction "1_1") (pintype "passive"))
      (node (ref "C9") (pin "1") (pinfunction "1_1") (pintype "passive"))
      (node (ref "R1") (pin "1") (pinfunction "1_1") (pintype "passive"))
      (node (ref "R10") (pin "1") (pinfunction "1_1") (pintype "passive"))
      (node (ref "R11") (pin "1") (pinfunction "1_1") (pintype "passive"))
      (node (ref "R12") (pin "1") (pinfunction "1_1") (pintype "passive"))
      (node (ref "R13") (pin "1") (pinfunction "1_1") (pintype "passive"))
      (node (ref "R14") (pin "1") (pinfunction "1_1") (pintype "passive"))
      (node (ref "R15") (pin "1") (pinfunction "1_1") (pintype "passive"))
      (node (ref "R16") (pin "1") (pinfunction "1_1") (pintype "passive"))
      (node (ref "R17") (pin "2") (pinfunction "2_2") (pintype "passive"))
      (node (ref "R2") (pin "1") (pinfunction "1_1") (pintype "passive"))
      (node (ref "R3") (pin "1") (pinfunction "1_1") (pintype "passive"))
      (node (ref "R4") (pin "1") (pinfunction "1_1") (pintype "passive"))
      (node (ref "R5") (pin "1") (pinfunction "1_1") (pintype "passive"))
      (node (ref "R6") (pin "1") (pinfunction "1_1") (pintype "passive"))
      (node (ref "R7") (pin "1") (pinfunction "1_1") (pintype "passive"))
      (node (ref "R8") (pin "1") (pinfunction "1_1") (pintype "passive"))
      (node (ref "R9") (pin "1") (pinfunction "1_1") (pintype "passive"))
      (node (ref "RN10") (pin "1") (pinfunction "1_1") (pintype "passive"))
      (node (ref "RN11") (pin "1") (pinfunction "1_1") (pintype "passive"))
      (node (ref "RN12") (pin "1") (pinfunction "1_1") (pintype "passive"))
      (node (ref "RN13") (pin "1") (pinfunction "1_1") (pintype "passive"))
      (node (ref "RN14") (pin "1") (pinfunction "1_1") (pintype "passive"))
      (node (ref "RN15") (pin "1") (pinfunction "1_1") (pintype "passive"))
      (node (ref "RN16") (pin "1") (pinfunction "1_1") (pintype "passive"))
      (node (ref "RN17") (pin "1") (pinfunction "1_1") (pintype "passive"))
      (node (ref "RN2") (pin "1") (pinfunction "1_1") (pintype "passive"))
      (node (ref "RN3") (pin "1") (pinfunction "1_1") (pintype "passive"))
      (node (ref "RN4") (pin "1") (pinfunction "1_1") (pintype "passive"))
      (node (ref "RN5") (pin "1") (pinfunction "1_1") (pintype "passive"))
      (node (ref "RN6") (pin "1") (pinfunction "1_1") (pintype "passive"))
      (node (ref "RN7") (pin "1") (pinfunction "1_1") (pintype "passive"))
      (node (ref "RN8") (pin "1") (pinfunction "1_1") (pintype "passive"))
      (node (ref "RN9") (pin "1") (pinfunction "1_1") (pintype "passive"))
      (node (ref "SW1") (pin "1") (pinfunction "1_1") (pintype "passive"))
      (node (ref "SW1") (pin "2") (pinfunction "2_2") (pintype "passive"))
      (node (ref "SW1") (pin "3") (pinfunction "3_3") (pintype "passive"))
      (node (ref "SW1") (pin "4") (pinfunction "4_4") (pintype "passive"))
      (node (ref "V1") (pin "14") (pinfunction "+UB_14") (pintype "power_in"))
      (node (ref "X1") (pin "A2") (pinfunction "B_A2") (pintype "passive"))
      (node (ref "X1") (pin "A31") (pinfunction "B_A31") (pintype "passive"))
      (node (ref "X1") (pin "B2") (pinfunction "B_B2") (pintype "passive"))
      (node (ref "X1") (pin "B31") (pinfunction "B_B31") (pintype "passive"))
      (node (ref "X1") (pin "C2") (pinfunction "B_C2") (pintype "passive"))
      (node (ref "X1") (pin "C31") (pinfunction "B_C31") (pintype "passive"))
    )
    (net (code "257") (name "unconnected-(IC4A-A<B_O-Pad7)") (class "Default")
      (node (ref "IC4") (pin "7") (pinfunction "A<B_O_7") (pintype "output"))
    )
    (net (code "258") (name "unconnected-(IC4A-A>B_O-Pad5)") (class "Default")
      (node (ref "IC4") (pin "5") (pinfunction "A>B_O_5") (pintype "output"))
    )
    (net (code "259") (name "unconnected-(V1C-Y-Pad1)") (class "Default")
      (node (ref "V1") (pin "1") (pinfunction "Y_1") (pintype "output"))
    )
  )
)
